# rc_filter_v1-xld50.net
KiCad netlist of a schematic drawn in EAGLE
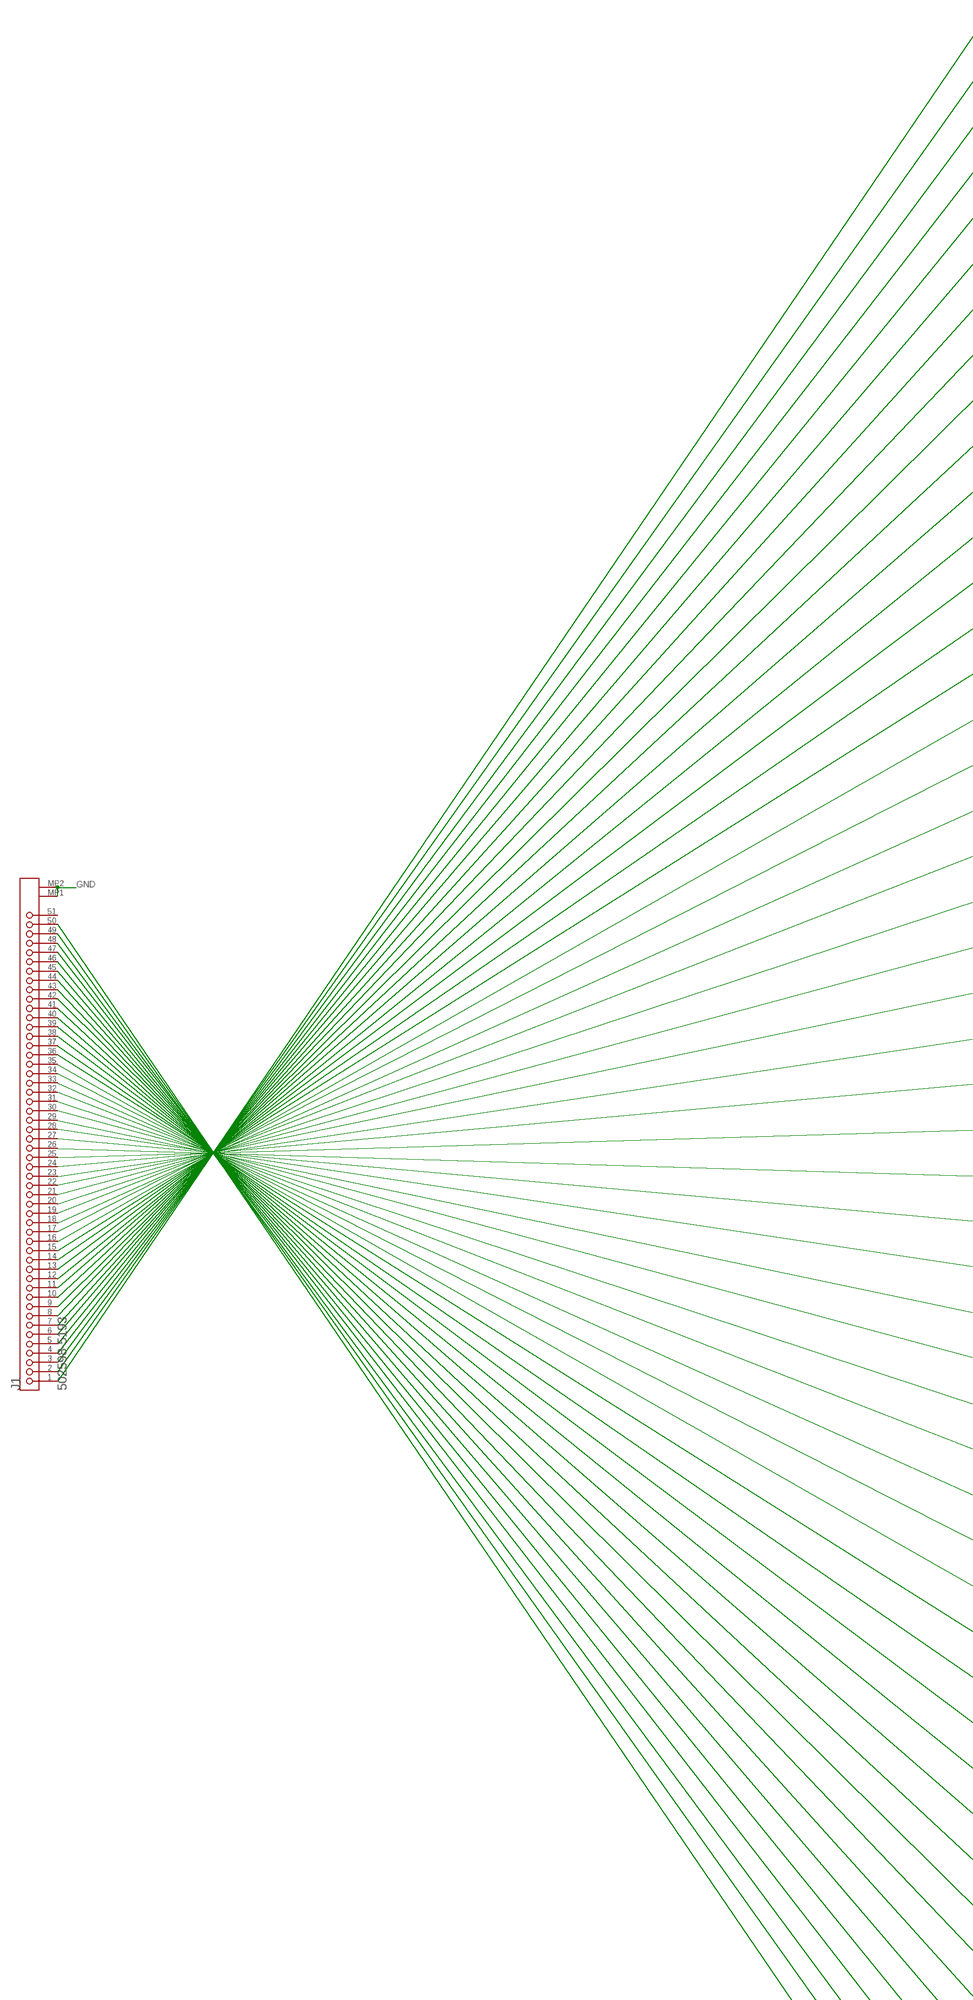
[diagram p0: schematic, sheet 1, part 1 of 3]
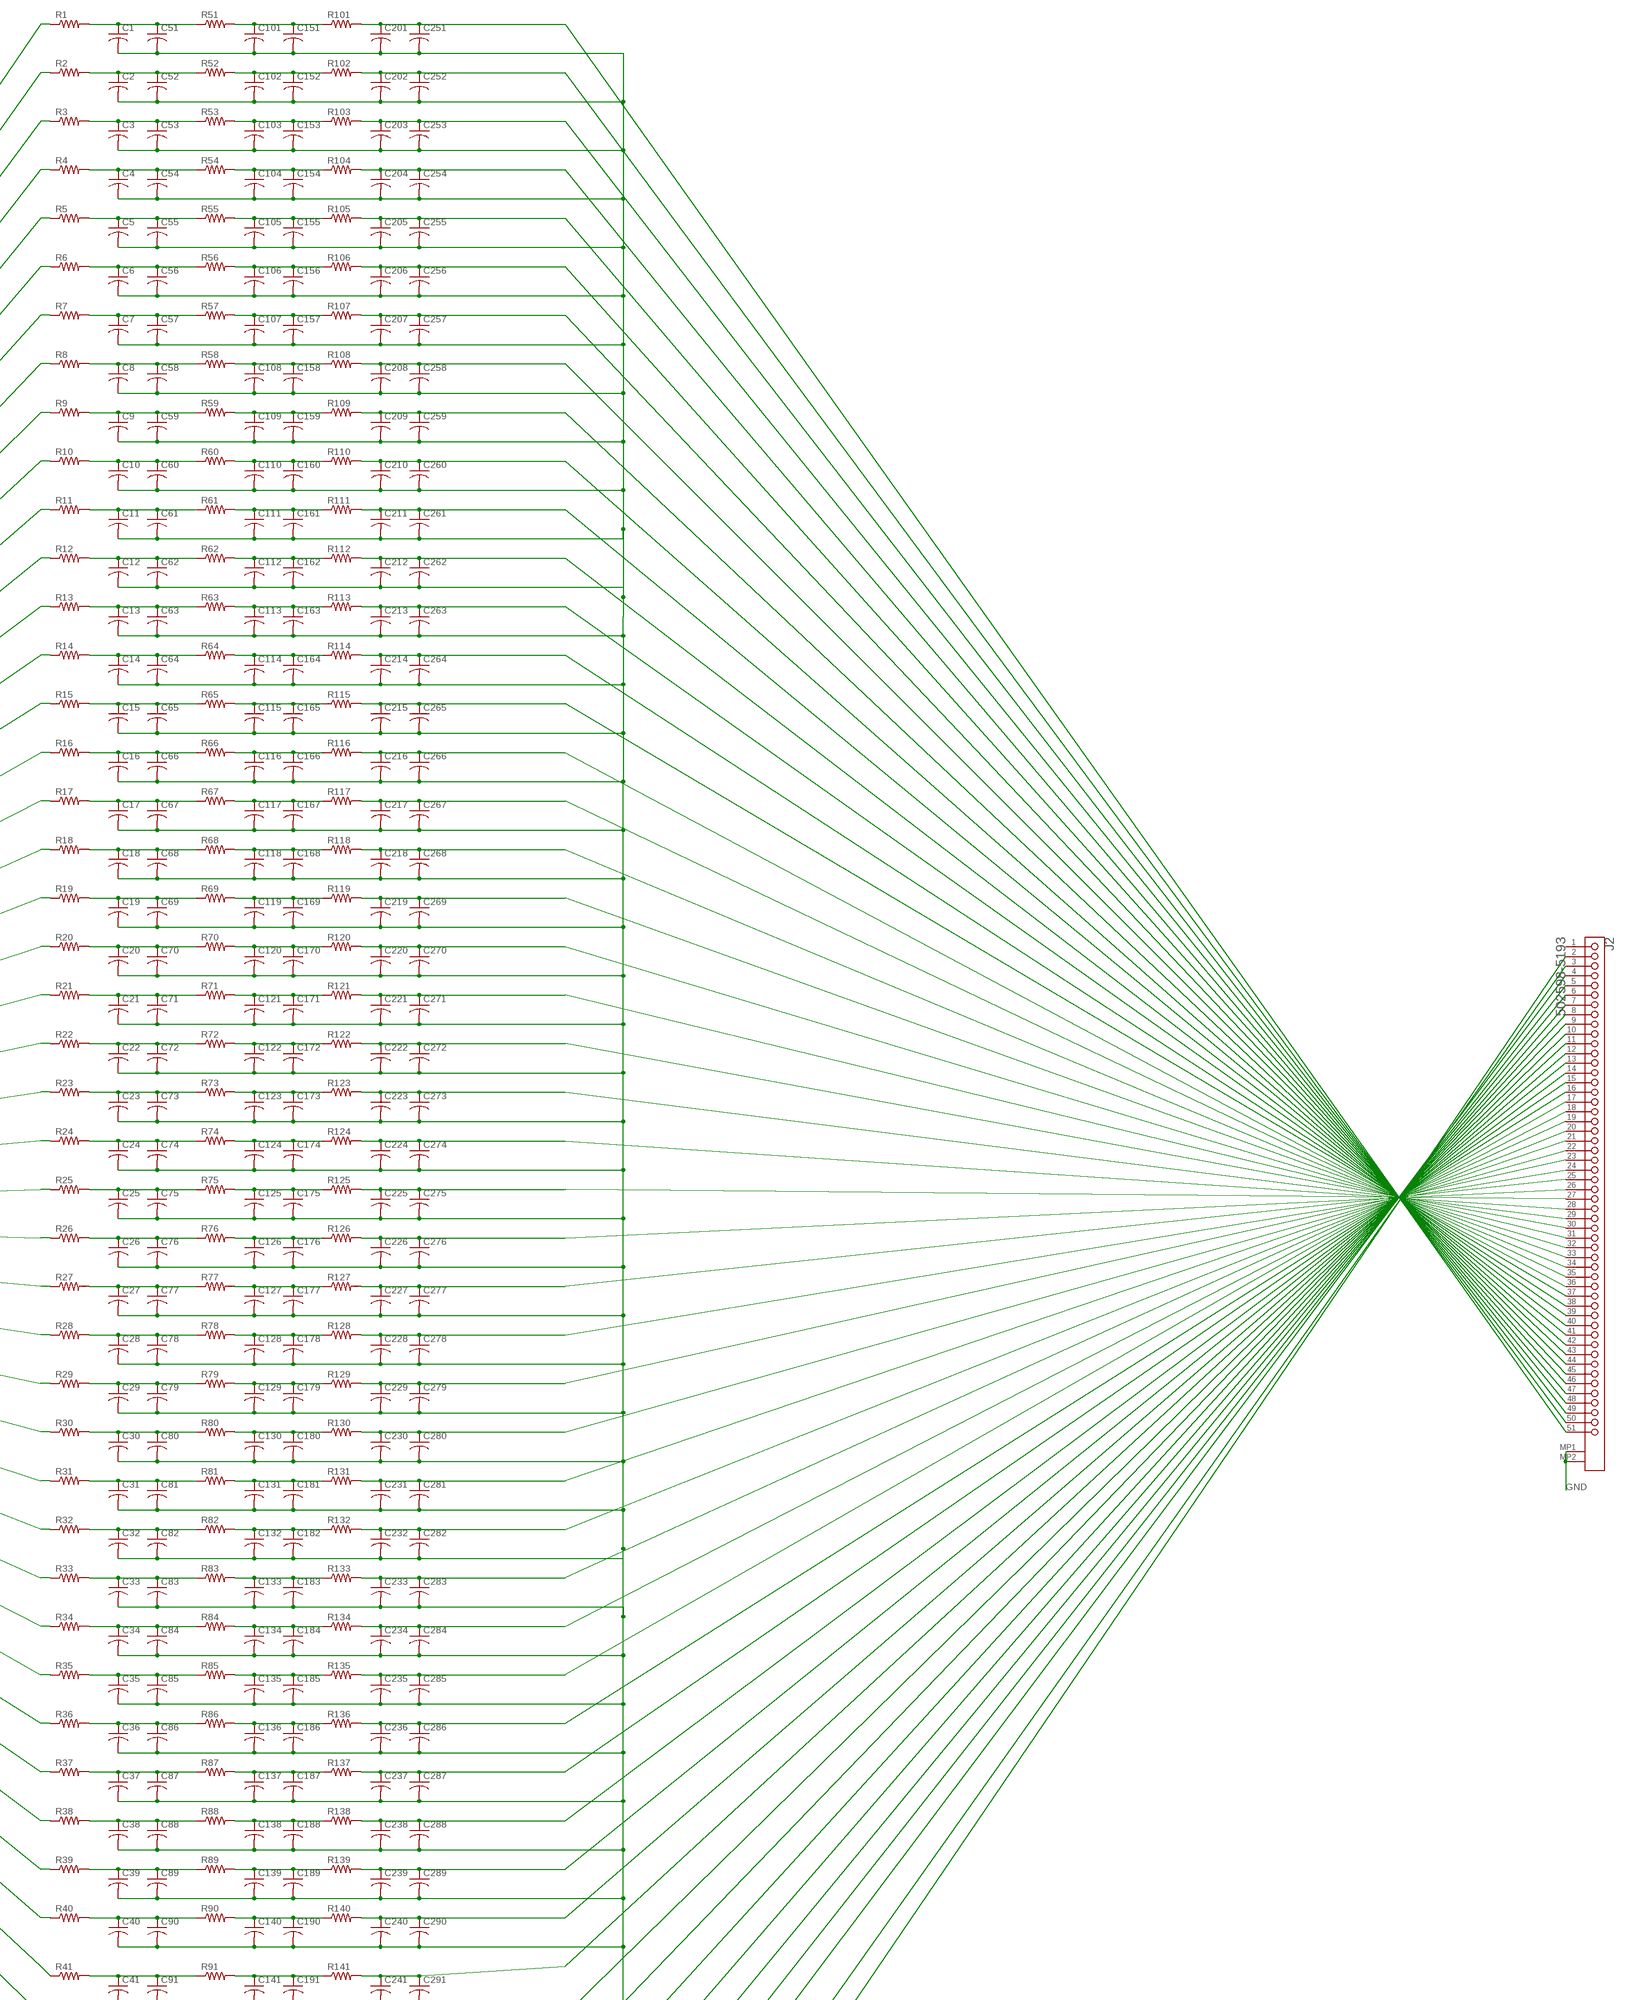
[diagram p1: schematic, sheet 1, part 2 of 3]
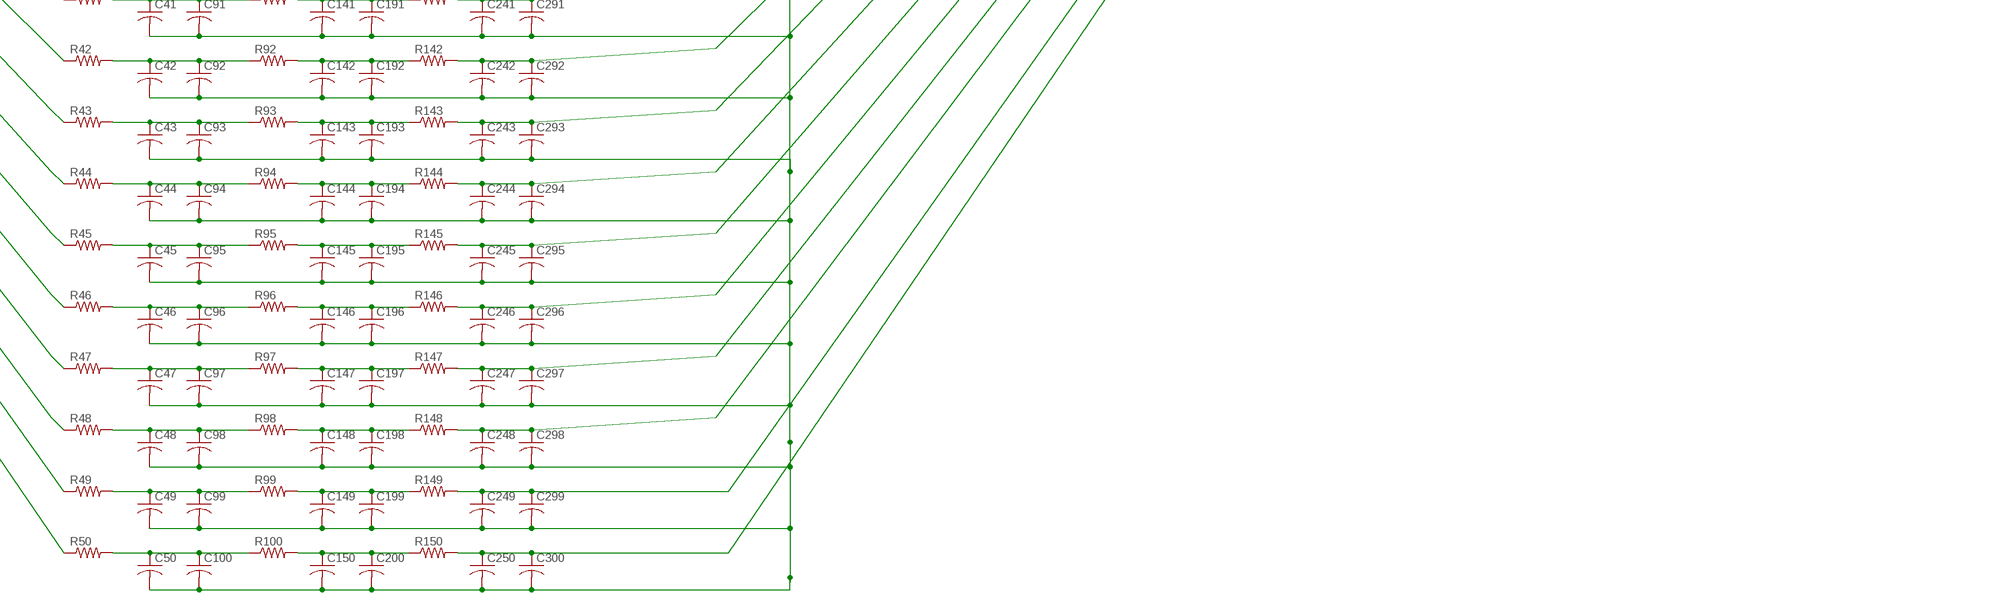
[diagram p2: schematic, sheet 1, part 3 of 3]

(export (version "E")
  (design (tool "Eeschema 10.0.6"))
  (components
    (comp (ref "C1")
      (value "C-USC0402")
      (footprint "eagle-import:C0402")
      (libsource (lib "eagle-import") (part "C-USC0402"))
    )
    (comp (ref "C2")
      (value "C-USC0402")
      (footprint "eagle-import:C0402")
      (libsource (lib "eagle-import") (part "C-USC0402"))
    )
    (comp (ref "C3")
      (value "C-USC0402")
      (footprint "eagle-import:C0402")
      (libsource (lib "eagle-import") (part "C-USC0402"))
    )
    (comp (ref "C4")
      (value "C-USC0402")
      (footprint "eagle-import:C0402")
      (libsource (lib "eagle-import") (part "C-USC0402"))
    )
    (comp (ref "C5")
      (value "C-USC0402")
      (footprint "eagle-import:C0402")
      (libsource (lib "eagle-import") (part "C-USC0402"))
    )
    (comp (ref "C6")
      (value "C-USC0402")
      (footprint "eagle-import:C0402")
      (libsource (lib "eagle-import") (part "C-USC0402"))
    )
    (comp (ref "C7")
      (value "C-USC0402")
      (footprint "eagle-import:C0402")
      (libsource (lib "eagle-import") (part "C-USC0402"))
    )
    (comp (ref "C8")
      (value "C-USC0402")
      (footprint "eagle-import:C0402")
      (libsource (lib "eagle-import") (part "C-USC0402"))
    )
    (comp (ref "C9")
      (value "C-USC0402")
      (footprint "eagle-import:C0402")
      (libsource (lib "eagle-import") (part "C-USC0402"))
    )
    (comp (ref "C10")
      (value "C-USC0402")
      (footprint "eagle-import:C0402")
      (libsource (lib "eagle-import") (part "C-USC0402"))
    )
    (comp (ref "C11")
      (value "C-USC0402")
      (footprint "eagle-import:C0402")
      (libsource (lib "eagle-import") (part "C-USC0402"))
    )
    (comp (ref "C12")
      (value "C-USC0402")
      (footprint "eagle-import:C0402")
      (libsource (lib "eagle-import") (part "C-USC0402"))
    )
    (comp (ref "C13")
      (value "C-USC0402")
      (footprint "eagle-import:C0402")
      (libsource (lib "eagle-import") (part "C-USC0402"))
    )
    (comp (ref "C14")
      (value "C-USC0402")
      (footprint "eagle-import:C0402")
      (libsource (lib "eagle-import") (part "C-USC0402"))
    )
    (comp (ref "C15")
      (value "C-USC0402")
      (footprint "eagle-import:C0402")
      (libsource (lib "eagle-import") (part "C-USC0402"))
    )
    (comp (ref "C16")
      (value "C-USC0402")
      (footprint "eagle-import:C0402")
      (libsource (lib "eagle-import") (part "C-USC0402"))
    )
    (comp (ref "C17")
      (value "C-USC0402")
      (footprint "eagle-import:C0402")
      (libsource (lib "eagle-import") (part "C-USC0402"))
    )
    (comp (ref "C18")
      (value "C-USC0402")
      (footprint "eagle-import:C0402")
      (libsource (lib "eagle-import") (part "C-USC0402"))
    )
    (comp (ref "C19")
      (value "C-USC0402")
      (footprint "eagle-import:C0402")
      (libsource (lib "eagle-import") (part "C-USC0402"))
    )
    (comp (ref "C20")
      (value "C-USC0402")
      (footprint "eagle-import:C0402")
      (libsource (lib "eagle-import") (part "C-USC0402"))
    )
    (comp (ref "C21")
      (value "C-USC0402")
      (footprint "eagle-import:C0402")
      (libsource (lib "eagle-import") (part "C-USC0402"))
    )
    (comp (ref "C22")
      (value "C-USC0402")
      (footprint "eagle-import:C0402")
      (libsource (lib "eagle-import") (part "C-USC0402"))
    )
    (comp (ref "C23")
      (value "C-USC0402")
      (footprint "eagle-import:C0402")
      (libsource (lib "eagle-import") (part "C-USC0402"))
    )
    (comp (ref "C24")
      (value "C-USC0402")
      (footprint "eagle-import:C0402")
      (libsource (lib "eagle-import") (part "C-USC0402"))
    )
    (comp (ref "C25")
      (value "C-USC0402")
      (footprint "eagle-import:C0402")
      (libsource (lib "eagle-import") (part "C-USC0402"))
    )
    (comp (ref "C26")
      (value "C-USC0402")
      (footprint "eagle-import:C0402")
      (libsource (lib "eagle-import") (part "C-USC0402"))
    )
    (comp (ref "C27")
      (value "C-USC0402")
      (footprint "eagle-import:C0402")
      (libsource (lib "eagle-import") (part "C-USC0402"))
    )
    (comp (ref "C28")
      (value "C-USC0402")
      (footprint "eagle-import:C0402")
      (libsource (lib "eagle-import") (part "C-USC0402"))
    )
    (comp (ref "C29")
      (value "C-USC0402")
      (footprint "eagle-import:C0402")
      (libsource (lib "eagle-import") (part "C-USC0402"))
    )
    (comp (ref "C30")
      (value "C-USC0402")
      (footprint "eagle-import:C0402")
      (libsource (lib "eagle-import") (part "C-USC0402"))
    )
    (comp (ref "C31")
      (value "C-USC0402")
      (footprint "eagle-import:C0402")
      (libsource (lib "eagle-import") (part "C-USC0402"))
    )
    (comp (ref "C32")
      (value "C-USC0402")
      (footprint "eagle-import:C0402")
      (libsource (lib "eagle-import") (part "C-USC0402"))
    )
    (comp (ref "C33")
      (value "C-USC0402")
      (footprint "eagle-import:C0402")
      (libsource (lib "eagle-import") (part "C-USC0402"))
    )
    (comp (ref "C34")
      (value "C-USC0402")
      (footprint "eagle-import:C0402")
      (libsource (lib "eagle-import") (part "C-USC0402"))
    )
    (comp (ref "C35")
      (value "C-USC0402")
      (footprint "eagle-import:C0402")
      (libsource (lib "eagle-import") (part "C-USC0402"))
    )
    (comp (ref "C36")
      (value "C-USC0402")
      (footprint "eagle-import:C0402")
      (libsource (lib "eagle-import") (part "C-USC0402"))
    )
    (comp (ref "C37")
      (value "C-USC0402")
      (footprint "eagle-import:C0402")
      (libsource (lib "eagle-import") (part "C-USC0402"))
    )
    (comp (ref "C38")
      (value "C-USC0402")
      (footprint "eagle-import:C0402")
      (libsource (lib "eagle-import") (part "C-USC0402"))
    )
    (comp (ref "C39")
      (value "C-USC0402")
      (footprint "eagle-import:C0402")
      (libsource (lib "eagle-import") (part "C-USC0402"))
    )
    (comp (ref "C40")
      (value "C-USC0402")
      (footprint "eagle-import:C0402")
      (libsource (lib "eagle-import") (part "C-USC0402"))
    )
    (comp (ref "C41")
      (value "C-USC0402")
      (footprint "eagle-import:C0402")
      (libsource (lib "eagle-import") (part "C-USC0402"))
    )
    (comp (ref "C42")
      (value "C-USC0402")
      (footprint "eagle-import:C0402")
      (libsource (lib "eagle-import") (part "C-USC0402"))
    )
    (comp (ref "C43")
      (value "C-USC0402")
      (footprint "eagle-import:C0402")
      (libsource (lib "eagle-import") (part "C-USC0402"))
    )
    (comp (ref "C44")
      (value "C-USC0402")
      (footprint "eagle-import:C0402")
      (libsource (lib "eagle-import") (part "C-USC0402"))
    )
    (comp (ref "C45")
      (value "C-USC0402")
      (footprint "eagle-import:C0402")
      (libsource (lib "eagle-import") (part "C-USC0402"))
    )
    (comp (ref "C46")
      (value "C-USC0402")
      (footprint "eagle-import:C0402")
      (libsource (lib "eagle-import") (part "C-USC0402"))
    )
    (comp (ref "C47")
      (value "C-USC0402")
      (footprint "eagle-import:C0402")
      (libsource (lib "eagle-import") (part "C-USC0402"))
    )
    (comp (ref "C48")
      (value "C-USC0402")
      (footprint "eagle-import:C0402")
      (libsource (lib "eagle-import") (part "C-USC0402"))
    )
    (comp (ref "C49")
      (value "C-USC0402")
      (footprint "eagle-import:C0402")
      (libsource (lib "eagle-import") (part "C-USC0402"))
    )
    (comp (ref "C50")
      (value "C-USC0402")
      (footprint "eagle-import:C0402")
      (libsource (lib "eagle-import") (part "C-USC0402"))
    )
    (comp (ref "C51")
      (value "C-USC0402")
      (footprint "eagle-import:C0402")
      (libsource (lib "eagle-import") (part "C-USC0402"))
    )
    (comp (ref "C52")
      (value "C-USC0402")
      (footprint "eagle-import:C0402")
      (libsource (lib "eagle-import") (part "C-USC0402"))
    )
    (comp (ref "C53")
      (value "C-USC0402")
      (footprint "eagle-import:C0402")
      (libsource (lib "eagle-import") (part "C-USC0402"))
    )
    (comp (ref "C54")
      (value "C-USC0402")
      (footprint "eagle-import:C0402")
      (libsource (lib "eagle-import") (part "C-USC0402"))
    )
    (comp (ref "C55")
      (value "C-USC0402")
      (footprint "eagle-import:C0402")
      (libsource (lib "eagle-import") (part "C-USC0402"))
    )
    (comp (ref "C56")
      (value "C-USC0402")
      (footprint "eagle-import:C0402")
      (libsource (lib "eagle-import") (part "C-USC0402"))
    )
    (comp (ref "C57")
      (value "C-USC0402")
      (footprint "eagle-import:C0402")
      (libsource (lib "eagle-import") (part "C-USC0402"))
    )
    (comp (ref "C58")
      (value "C-USC0402")
      (footprint "eagle-import:C0402")
      (libsource (lib "eagle-import") (part "C-USC0402"))
    )
    (comp (ref "C59")
      (value "C-USC0402")
      (footprint "eagle-import:C0402")
      (libsource (lib "eagle-import") (part "C-USC0402"))
    )
    (comp (ref "C60")
      (value "C-USC0402")
      (footprint "eagle-import:C0402")
      (libsource (lib "eagle-import") (part "C-USC0402"))
    )
    (comp (ref "C61")
      (value "C-USC0402")
      (footprint "eagle-import:C0402")
      (libsource (lib "eagle-import") (part "C-USC0402"))
    )
    (comp (ref "C62")
      (value "C-USC0402")
      (footprint "eagle-import:C0402")
      (libsource (lib "eagle-import") (part "C-USC0402"))
    )
    (comp (ref "C63")
      (value "C-USC0402")
      (footprint "eagle-import:C0402")
      (libsource (lib "eagle-import") (part "C-USC0402"))
    )
    (comp (ref "C64")
      (value "C-USC0402")
      (footprint "eagle-import:C0402")
      (libsource (lib "eagle-import") (part "C-USC0402"))
    )
    (comp (ref "C65")
      (value "C-USC0402")
      (footprint "eagle-import:C0402")
      (libsource (lib "eagle-import") (part "C-USC0402"))
    )
    (comp (ref "C66")
      (value "C-USC0402")
      (footprint "eagle-import:C0402")
      (libsource (lib "eagle-import") (part "C-USC0402"))
    )
    (comp (ref "C67")
      (value "C-USC0402")
      (footprint "eagle-import:C0402")
      (libsource (lib "eagle-import") (part "C-USC0402"))
    )
    (comp (ref "C68")
      (value "C-USC0402")
      (footprint "eagle-import:C0402")
      (libsource (lib "eagle-import") (part "C-USC0402"))
    )
    (comp (ref "C69")
      (value "C-USC0402")
      (footprint "eagle-import:C0402")
      (libsource (lib "eagle-import") (part "C-USC0402"))
    )
    (comp (ref "C70")
      (value "C-USC0402")
      (footprint "eagle-import:C0402")
      (libsource (lib "eagle-import") (part "C-USC0402"))
    )
    (comp (ref "C71")
      (value "C-USC0402")
      (footprint "eagle-import:C0402")
      (libsource (lib "eagle-import") (part "C-USC0402"))
    )
    (comp (ref "C72")
      (value "C-USC0402")
      (footprint "eagle-import:C0402")
      (libsource (lib "eagle-import") (part "C-USC0402"))
    )
    (comp (ref "C73")
      (value "C-USC0402")
      (footprint "eagle-import:C0402")
      (libsource (lib "eagle-import") (part "C-USC0402"))
    )
    (comp (ref "C74")
      (value "C-USC0402")
      (footprint "eagle-import:C0402")
      (libsource (lib "eagle-import") (part "C-USC0402"))
    )
    (comp (ref "C75")
      (value "C-USC0402")
      (footprint "eagle-import:C0402")
      (libsource (lib "eagle-import") (part "C-USC0402"))
    )
    (comp (ref "C76")
      (value "C-USC0402")
      (footprint "eagle-import:C0402")
      (libsource (lib "eagle-import") (part "C-USC0402"))
    )
    (comp (ref "C77")
      (value "C-USC0402")
      (footprint "eagle-import:C0402")
      (libsource (lib "eagle-import") (part "C-USC0402"))
    )
    (comp (ref "C78")
      (value "C-USC0402")
      (footprint "eagle-import:C0402")
      (libsource (lib "eagle-import") (part "C-USC0402"))
    )
    (comp (ref "C79")
      (value "C-USC0402")
      (footprint "eagle-import:C0402")
      (libsource (lib "eagle-import") (part "C-USC0402"))
    )
    (comp (ref "C80")
      (value "C-USC0402")
      (footprint "eagle-import:C0402")
      (libsource (lib "eagle-import") (part "C-USC0402"))
    )
    (comp (ref "C81")
      (value "C-USC0402")
      (footprint "eagle-import:C0402")
      (libsource (lib "eagle-import") (part "C-USC0402"))
    )
    (comp (ref "C82")
      (value "C-USC0402")
      (footprint "eagle-import:C0402")
      (libsource (lib "eagle-import") (part "C-USC0402"))
    )
    (comp (ref "C83")
      (value "C-USC0402")
      (footprint "eagle-import:C0402")
      (libsource (lib "eagle-import") (part "C-USC0402"))
    )
    (comp (ref "C84")
      (value "C-USC0402")
      (footprint "eagle-import:C0402")
      (libsource (lib "eagle-import") (part "C-USC0402"))
    )
    (comp (ref "C85")
      (value "C-USC0402")
      (footprint "eagle-import:C0402")
      (libsource (lib "eagle-import") (part "C-USC0402"))
    )
    (comp (ref "C86")
      (value "C-USC0402")
      (footprint "eagle-import:C0402")
      (libsource (lib "eagle-import") (part "C-USC0402"))
    )
    (comp (ref "C87")
      (value "C-USC0402")
      (footprint "eagle-import:C0402")
      (libsource (lib "eagle-import") (part "C-USC0402"))
    )
    (comp (ref "C88")
      (value "C-USC0402")
      (footprint "eagle-import:C0402")
      (libsource (lib "eagle-import") (part "C-USC0402"))
    )
    (comp (ref "C89")
      (value "C-USC0402")
      (footprint "eagle-import:C0402")
      (libsource (lib "eagle-import") (part "C-USC0402"))
    )
    (comp (ref "C90")
      (value "C-USC0402")
      (footprint "eagle-import:C0402")
      (libsource (lib "eagle-import") (part "C-USC0402"))
    )
    (comp (ref "C91")
      (value "C-USC0402")
      (footprint "eagle-import:C0402")
      (libsource (lib "eagle-import") (part "C-USC0402"))
    )
    (comp (ref "C92")
      (value "C-USC0402")
      (footprint "eagle-import:C0402")
      (libsource (lib "eagle-import") (part "C-USC0402"))
    )
    (comp (ref "C93")
      (value "C-USC0402")
      (footprint "eagle-import:C0402")
      (libsource (lib "eagle-import") (part "C-USC0402"))
    )
    (comp (ref "C94")
      (value "C-USC0402")
      (footprint "eagle-import:C0402")
      (libsource (lib "eagle-import") (part "C-USC0402"))
    )
    (comp (ref "C95")
      (value "C-USC0402")
      (footprint "eagle-import:C0402")
      (libsource (lib "eagle-import") (part "C-USC0402"))
    )
    (comp (ref "C96")
      (value "C-USC0402")
      (footprint "eagle-import:C0402")
      (libsource (lib "eagle-import") (part "C-USC0402"))
    )
    (comp (ref "C97")
      (value "C-USC0402")
      (footprint "eagle-import:C0402")
      (libsource (lib "eagle-import") (part "C-USC0402"))
    )
    (comp (ref "C98")
      (value "C-USC0402")
      (footprint "eagle-import:C0402")
      (libsource (lib "eagle-import") (part "C-USC0402"))
    )
    (comp (ref "C99")
      (value "C-USC0402")
      (footprint "eagle-import:C0402")
      (libsource (lib "eagle-import") (part "C-USC0402"))
    )
    (comp (ref "C100")
      (value "C-USC0402")
      (footprint "eagle-import:C0402")
      (libsource (lib "eagle-import") (part "C-USC0402"))
    )
    (comp (ref "C101")
      (value "C-USC0402")
      (footprint "eagle-import:C0402")
      (libsource (lib "eagle-import") (part "C-USC0402"))
    )
    (comp (ref "C102")
      (value "C-USC0402")
      (footprint "eagle-import:C0402")
      (libsource (lib "eagle-import") (part "C-USC0402"))
    )
    (comp (ref "C103")
      (value "C-USC0402")
      (footprint "eagle-import:C0402")
      (libsource (lib "eagle-import") (part "C-USC0402"))
    )
    (comp (ref "C104")
      (value "C-USC0402")
      (footprint "eagle-import:C0402")
      (libsource (lib "eagle-import") (part "C-USC0402"))
    )
    (comp (ref "C105")
      (value "C-USC0402")
      (footprint "eagle-import:C0402")
      (libsource (lib "eagle-import") (part "C-USC0402"))
    )
    (comp (ref "C106")
      (value "C-USC0402")
      (footprint "eagle-import:C0402")
      (libsource (lib "eagle-import") (part "C-USC0402"))
    )
    (comp (ref "C107")
      (value "C-USC0402")
      (footprint "eagle-import:C0402")
      (libsource (lib "eagle-import") (part "C-USC0402"))
    )
    (comp (ref "C108")
      (value "C-USC0402")
      (footprint "eagle-import:C0402")
      (libsource (lib "eagle-import") (part "C-USC0402"))
    )
    (comp (ref "C109")
      (value "C-USC0402")
      (footprint "eagle-import:C0402")
      (libsource (lib "eagle-import") (part "C-USC0402"))
    )
    (comp (ref "C110")
      (value "C-USC0402")
      (footprint "eagle-import:C0402")
      (libsource (lib "eagle-import") (part "C-USC0402"))
    )
    (comp (ref "C111")
      (value "C-USC0402")
      (footprint "eagle-import:C0402")
      (libsource (lib "eagle-import") (part "C-USC0402"))
    )
    (comp (ref "C112")
      (value "C-USC0402")
      (footprint "eagle-import:C0402")
      (libsource (lib "eagle-import") (part "C-USC0402"))
    )
    (comp (ref "C113")
      (value "C-USC0402")
      (footprint "eagle-import:C0402")
      (libsource (lib "eagle-import") (part "C-USC0402"))
    )
    (comp (ref "C114")
      (value "C-USC0402")
      (footprint "eagle-import:C0402")
      (libsource (lib "eagle-import") (part "C-USC0402"))
    )
    (comp (ref "C115")
      (value "C-USC0402")
      (footprint "eagle-import:C0402")
      (libsource (lib "eagle-import") (part "C-USC0402"))
    )
    (comp (ref "C116")
      (value "C-USC0402")
      (footprint "eagle-import:C0402")
      (libsource (lib "eagle-import") (part "C-USC0402"))
    )
    (comp (ref "C117")
      (value "C-USC0402")
      (footprint "eagle-import:C0402")
      (libsource (lib "eagle-import") (part "C-USC0402"))
    )
    (comp (ref "C118")
      (value "C-USC0402")
      (footprint "eagle-import:C0402")
      (libsource (lib "eagle-import") (part "C-USC0402"))
    )
    (comp (ref "C119")
      (value "C-USC0402")
      (footprint "eagle-import:C0402")
      (libsource (lib "eagle-import") (part "C-USC0402"))
    )
    (comp (ref "C120")
      (value "C-USC0402")
      (footprint "eagle-import:C0402")
      (libsource (lib "eagle-import") (part "C-USC0402"))
    )
    (comp (ref "C121")
      (value "C-USC0402")
      (footprint "eagle-import:C0402")
      (libsource (lib "eagle-import") (part "C-USC0402"))
    )
    (comp (ref "C122")
      (value "C-USC0402")
      (footprint "eagle-import:C0402")
      (libsource (lib "eagle-import") (part "C-USC0402"))
    )
    (comp (ref "C123")
      (value "C-USC0402")
      (footprint "eagle-import:C0402")
      (libsource (lib "eagle-import") (part "C-USC0402"))
    )
    (comp (ref "C124")
      (value "C-USC0402")
      (footprint "eagle-import:C0402")
      (libsource (lib "eagle-import") (part "C-USC0402"))
    )
    (comp (ref "C125")
      (value "C-USC0402")
      (footprint "eagle-import:C0402")
      (libsource (lib "eagle-import") (part "C-USC0402"))
    )
    (comp (ref "C126")
      (value "C-USC0402")
      (footprint "eagle-import:C0402")
      (libsource (lib "eagle-import") (part "C-USC0402"))
    )
    (comp (ref "C127")
      (value "C-USC0402")
      (footprint "eagle-import:C0402")
      (libsource (lib "eagle-import") (part "C-USC0402"))
    )
    (comp (ref "C128")
      (value "C-USC0402")
      (footprint "eagle-import:C0402")
      (libsource (lib "eagle-import") (part "C-USC0402"))
    )
    (comp (ref "C129")
      (value "C-USC0402")
      (footprint "eagle-import:C0402")
      (libsource (lib "eagle-import") (part "C-USC0402"))
    )
    (comp (ref "C130")
      (value "C-USC0402")
      (footprint "eagle-import:C0402")
      (libsource (lib "eagle-import") (part "C-USC0402"))
    )
    (comp (ref "C131")
      (value "C-USC0402")
      (footprint "eagle-import:C0402")
      (libsource (lib "eagle-import") (part "C-USC0402"))
    )
    (comp (ref "C132")
      (value "C-USC0402")
      (footprint "eagle-import:C0402")
      (libsource (lib "eagle-import") (part "C-USC0402"))
    )
    (comp (ref "C133")
      (value "C-USC0402")
      (footprint "eagle-import:C0402")
      (libsource (lib "eagle-import") (part "C-USC0402"))
    )
    (comp (ref "C134")
      (value "C-USC0402")
      (footprint "eagle-import:C0402")
      (libsource (lib "eagle-import") (part "C-USC0402"))
    )
    (comp (ref "C135")
      (value "C-USC0402")
      (footprint "eagle-import:C0402")
      (libsource (lib "eagle-import") (part "C-USC0402"))
    )
    (comp (ref "C136")
      (value "C-USC0402")
      (footprint "eagle-import:C0402")
      (libsource (lib "eagle-import") (part "C-USC0402"))
    )
    (comp (ref "C137")
      (value "C-USC0402")
      (footprint "eagle-import:C0402")
      (libsource (lib "eagle-import") (part "C-USC0402"))
    )
    (comp (ref "C138")
      (value "C-USC0402")
      (footprint "eagle-import:C0402")
      (libsource (lib "eagle-import") (part "C-USC0402"))
    )
    (comp (ref "C139")
      (value "C-USC0402")
      (footprint "eagle-import:C0402")
      (libsource (lib "eagle-import") (part "C-USC0402"))
    )
    (comp (ref "C140")
      (value "C-USC0402")
      (footprint "eagle-import:C0402")
      (libsource (lib "eagle-import") (part "C-USC0402"))
    )
    (comp (ref "C141")
      (value "C-USC0402")
      (footprint "eagle-import:C0402")
      (libsource (lib "eagle-import") (part "C-USC0402"))
    )
    (comp (ref "C142")
      (value "C-USC0402")
      (footprint "eagle-import:C0402")
      (libsource (lib "eagle-import") (part "C-USC0402"))
    )
    (comp (ref "C143")
      (value "C-USC0402")
      (footprint "eagle-import:C0402")
      (libsource (lib "eagle-import") (part "C-USC0402"))
    )
    (comp (ref "C144")
      (value "C-USC0402")
      (footprint "eagle-import:C0402")
      (libsource (lib "eagle-import") (part "C-USC0402"))
    )
    (comp (ref "C145")
      (value "C-USC0402")
      (footprint "eagle-import:C0402")
      (libsource (lib "eagle-import") (part "C-USC0402"))
    )
    (comp (ref "C146")
      (value "C-USC0402")
      (footprint "eagle-import:C0402")
      (libsource (lib "eagle-import") (part "C-USC0402"))
    )
    (comp (ref "C147")
      (value "C-USC0402")
      (footprint "eagle-import:C0402")
      (libsource (lib "eagle-import") (part "C-USC0402"))
    )
    (comp (ref "C148")
      (value "C-USC0402")
      (footprint "eagle-import:C0402")
      (libsource (lib "eagle-import") (part "C-USC0402"))
    )
    (comp (ref "C149")
      (value "C-USC0402")
      (footprint "eagle-import:C0402")
      (libsource (lib "eagle-import") (part "C-USC0402"))
    )
    (comp (ref "C150")
      (value "C-USC0402")
      (footprint "eagle-import:C0402")
      (libsource (lib "eagle-import") (part "C-USC0402"))
    )
    (comp (ref "C151")
      (value "C-USC0402")
      (footprint "eagle-import:C0402")
      (libsource (lib "eagle-import") (part "C-USC0402"))
    )
    (comp (ref "C152")
      (value "C-USC0402")
      (footprint "eagle-import:C0402")
      (libsource (lib "eagle-import") (part "C-USC0402"))
    )
    (comp (ref "C153")
      (value "C-USC0402")
      (footprint "eagle-import:C0402")
      (libsource (lib "eagle-import") (part "C-USC0402"))
    )
    (comp (ref "C154")
      (value "C-USC0402")
      (footprint "eagle-import:C0402")
      (libsource (lib "eagle-import") (part "C-USC0402"))
    )
    (comp (ref "C155")
      (value "C-USC0402")
      (footprint "eagle-import:C0402")
      (libsource (lib "eagle-import") (part "C-USC0402"))
    )
    (comp (ref "C156")
      (value "C-USC0402")
      (footprint "eagle-import:C0402")
      (libsource (lib "eagle-import") (part "C-USC0402"))
    )
    (comp (ref "C157")
      (value "C-USC0402")
      (footprint "eagle-import:C0402")
      (libsource (lib "eagle-import") (part "C-USC0402"))
    )
    (comp (ref "C158")
      (value "C-USC0402")
      (footprint "eagle-import:C0402")
      (libsource (lib "eagle-import") (part "C-USC0402"))
    )
    (comp (ref "C159")
      (value "C-USC0402")
      (footprint "eagle-import:C0402")
      (libsource (lib "eagle-import") (part "C-USC0402"))
    )
    (comp (ref "C160")
      (value "C-USC0402")
      (footprint "eagle-import:C0402")
      (libsource (lib "eagle-import") (part "C-USC0402"))
    )
    (comp (ref "C161")
      (value "C-USC0402")
      (footprint "eagle-import:C0402")
      (libsource (lib "eagle-import") (part "C-USC0402"))
    )
    (comp (ref "C162")
      (value "C-USC0402")
      (footprint "eagle-import:C0402")
      (libsource (lib "eagle-import") (part "C-USC0402"))
    )
    (comp (ref "C163")
      (value "C-USC0402")
      (footprint "eagle-import:C0402")
      (libsource (lib "eagle-import") (part "C-USC0402"))
    )
    (comp (ref "C164")
      (value "C-USC0402")
      (footprint "eagle-import:C0402")
      (libsource (lib "eagle-import") (part "C-USC0402"))
    )
    (comp (ref "C165")
      (value "C-USC0402")
      (footprint "eagle-import:C0402")
      (libsource (lib "eagle-import") (part "C-USC0402"))
    )
    (comp (ref "C166")
      (value "C-USC0402")
      (footprint "eagle-import:C0402")
      (libsource (lib "eagle-import") (part "C-USC0402"))
    )
    (comp (ref "C167")
      (value "C-USC0402")
      (footprint "eagle-import:C0402")
      (libsource (lib "eagle-import") (part "C-USC0402"))
    )
    (comp (ref "C168")
      (value "C-USC0402")
      (footprint "eagle-import:C0402")
      (libsource (lib "eagle-import") (part "C-USC0402"))
    )
    (comp (ref "C169")
      (value "C-USC0402")
      (footprint "eagle-import:C0402")
      (libsource (lib "eagle-import") (part "C-USC0402"))
    )
    (comp (ref "C170")
      (value "C-USC0402")
      (footprint "eagle-import:C0402")
      (libsource (lib "eagle-import") (part "C-USC0402"))
    )
    (comp (ref "C171")
      (value "C-USC0402")
      (footprint "eagle-import:C0402")
      (libsource (lib "eagle-import") (part "C-USC0402"))
    )
    (comp (ref "C172")
      (value "C-USC0402")
      (footprint "eagle-import:C0402")
      (libsource (lib "eagle-import") (part "C-USC0402"))
    )
    (comp (ref "C173")
      (value "C-USC0402")
      (footprint "eagle-import:C0402")
      (libsource (lib "eagle-import") (part "C-USC0402"))
    )
    (comp (ref "C174")
      (value "C-USC0402")
      (footprint "eagle-import:C0402")
      (libsource (lib "eagle-import") (part "C-USC0402"))
    )
    (comp (ref "C175")
      (value "C-USC0402")
      (footprint "eagle-import:C0402")
      (libsource (lib "eagle-import") (part "C-USC0402"))
    )
    (comp (ref "C176")
      (value "C-USC0402")
      (footprint "eagle-import:C0402")
      (libsource (lib "eagle-import") (part "C-USC0402"))
    )
    (comp (ref "C177")
      (value "C-USC0402")
      (footprint "eagle-import:C0402")
      (libsource (lib "eagle-import") (part "C-USC0402"))
    )
    (comp (ref "C178")
      (value "C-USC0402")
      (footprint "eagle-import:C0402")
      (libsource (lib "eagle-import") (part "C-USC0402"))
    )
    (comp (ref "C179")
      (value "C-USC0402")
      (footprint "eagle-import:C0402")
      (libsource (lib "eagle-import") (part "C-USC0402"))
    )
    (comp (ref "C180")
      (value "C-USC0402")
      (footprint "eagle-import:C0402")
      (libsource (lib "eagle-import") (part "C-USC0402"))
    )
    (comp (ref "C181")
      (value "C-USC0402")
      (footprint "eagle-import:C0402")
      (libsource (lib "eagle-import") (part "C-USC0402"))
    )
    (comp (ref "C182")
      (value "C-USC0402")
      (footprint "eagle-import:C0402")
      (libsource (lib "eagle-import") (part "C-USC0402"))
    )
    (comp (ref "C183")
      (value "C-USC0402")
      (footprint "eagle-import:C0402")
      (libsource (lib "eagle-import") (part "C-USC0402"))
    )
    (comp (ref "C184")
      (value "C-USC0402")
      (footprint "eagle-import:C0402")
      (libsource (lib "eagle-import") (part "C-USC0402"))
    )
    (comp (ref "C185")
      (value "C-USC0402")
      (footprint "eagle-import:C0402")
      (libsource (lib "eagle-import") (part "C-USC0402"))
    )
    (comp (ref "C186")
      (value "C-USC0402")
      (footprint "eagle-import:C0402")
      (libsource (lib "eagle-import") (part "C-USC0402"))
    )
    (comp (ref "C187")
      (value "C-USC0402")
      (footprint "eagle-import:C0402")
      (libsource (lib "eagle-import") (part "C-USC0402"))
    )
    (comp (ref "C188")
      (value "C-USC0402")
      (footprint "eagle-import:C0402")
      (libsource (lib "eagle-import") (part "C-USC0402"))
    )
    (comp (ref "C189")
      (value "C-USC0402")
      (footprint "eagle-import:C0402")
      (libsource (lib "eagle-import") (part "C-USC0402"))
    )
    (comp (ref "C190")
      (value "C-USC0402")
      (footprint "eagle-import:C0402")
      (libsource (lib "eagle-import") (part "C-USC0402"))
    )
    (comp (ref "C191")
      (value "C-USC0402")
      (footprint "eagle-import:C0402")
      (libsource (lib "eagle-import") (part "C-USC0402"))
    )
    (comp (ref "C192")
      (value "C-USC0402")
      (footprint "eagle-import:C0402")
      (libsource (lib "eagle-import") (part "C-USC0402"))
    )
    (comp (ref "C193")
      (value "C-USC0402")
      (footprint "eagle-import:C0402")
      (libsource (lib "eagle-import") (part "C-USC0402"))
    )
    (comp (ref "C194")
      (value "C-USC0402")
      (footprint "eagle-import:C0402")
      (libsource (lib "eagle-import") (part "C-USC0402"))
    )
    (comp (ref "C195")
      (value "C-USC0402")
      (footprint "eagle-import:C0402")
      (libsource (lib "eagle-import") (part "C-USC0402"))
    )
    (comp (ref "C196")
      (value "C-USC0402")
      (footprint "eagle-import:C0402")
      (libsource (lib "eagle-import") (part "C-USC0402"))
    )
    (comp (ref "C197")
      (value "C-USC0402")
      (footprint "eagle-import:C0402")
      (libsource (lib "eagle-import") (part "C-USC0402"))
    )
    (comp (ref "C198")
      (value "C-USC0402")
      (footprint "eagle-import:C0402")
      (libsource (lib "eagle-import") (part "C-USC0402"))
    )
    (comp (ref "C199")
      (value "C-USC0402")
      (footprint "eagle-import:C0402")
      (libsource (lib "eagle-import") (part "C-USC0402"))
    )
    (comp (ref "C200")
      (value "C-USC0402")
      (footprint "eagle-import:C0402")
      (libsource (lib "eagle-import") (part "C-USC0402"))
    )
    (comp (ref "C201")
      (value "C-USC0402")
      (footprint "eagle-import:C0402")
      (libsource (lib "eagle-import") (part "C-USC0402"))
    )
    (comp (ref "C202")
      (value "C-USC0402")
      (footprint "eagle-import:C0402")
      (libsource (lib "eagle-import") (part "C-USC0402"))
    )
    (comp (ref "C203")
      (value "C-USC0402")
      (footprint "eagle-import:C0402")
      (libsource (lib "eagle-import") (part "C-USC0402"))
    )
    (comp (ref "C204")
      (value "C-USC0402")
      (footprint "eagle-import:C0402")
      (libsource (lib "eagle-import") (part "C-USC0402"))
    )
    (comp (ref "C205")
      (value "C-USC0402")
      (footprint "eagle-import:C0402")
      (libsource (lib "eagle-import") (part "C-USC0402"))
    )
    (comp (ref "C206")
      (value "C-USC0402")
      (footprint "eagle-import:C0402")
      (libsource (lib "eagle-import") (part "C-USC0402"))
    )
    (comp (ref "C207")
      (value "C-USC0402")
      (footprint "eagle-import:C0402")
      (libsource (lib "eagle-import") (part "C-USC0402"))
    )
    (comp (ref "C208")
      (value "C-USC0402")
      (footprint "eagle-import:C0402")
      (libsource (lib "eagle-import") (part "C-USC0402"))
    )
    (comp (ref "C209")
      (value "C-USC0402")
      (footprint "eagle-import:C0402")
      (libsource (lib "eagle-import") (part "C-USC0402"))
    )
    (comp (ref "C210")
      (value "C-USC0402")
      (footprint "eagle-import:C0402")
      (libsource (lib "eagle-import") (part "C-USC0402"))
    )
    (comp (ref "C211")
      (value "C-USC0402")
      (footprint "eagle-import:C0402")
      (libsource (lib "eagle-import") (part "C-USC0402"))
    )
    (comp (ref "C212")
      (value "C-USC0402")
      (footprint "eagle-import:C0402")
      (libsource (lib "eagle-import") (part "C-USC0402"))
    )
    (comp (ref "C213")
      (value "C-USC0402")
      (footprint "eagle-import:C0402")
      (libsource (lib "eagle-import") (part "C-USC0402"))
    )
    (comp (ref "C214")
      (value "C-USC0402")
      (footprint "eagle-import:C0402")
      (libsource (lib "eagle-import") (part "C-USC0402"))
    )
    (comp (ref "C215")
      (value "C-USC0402")
      (footprint "eagle-import:C0402")
      (libsource (lib "eagle-import") (part "C-USC0402"))
    )
    (comp (ref "C216")
      (value "C-USC0402")
      (footprint "eagle-import:C0402")
      (libsource (lib "eagle-import") (part "C-USC0402"))
    )
    (comp (ref "C217")
      (value "C-USC0402")
      (footprint "eagle-import:C0402")
      (libsource (lib "eagle-import") (part "C-USC0402"))
    )
    (comp (ref "C218")
      (value "C-USC0402")
      (footprint "eagle-import:C0402")
      (libsource (lib "eagle-import") (part "C-USC0402"))
    )
    (comp (ref "C219")
      (value "C-USC0402")
      (footprint "eagle-import:C0402")
      (libsource (lib "eagle-import") (part "C-USC0402"))
    )
    (comp (ref "C220")
      (value "C-USC0402")
      (footprint "eagle-import:C0402")
      (libsource (lib "eagle-import") (part "C-USC0402"))
    )
    (comp (ref "C221")
      (value "C-USC0402")
      (footprint "eagle-import:C0402")
      (libsource (lib "eagle-import") (part "C-USC0402"))
    )
    (comp (ref "C222")
      (value "C-USC0402")
      (footprint "eagle-import:C0402")
      (libsource (lib "eagle-import") (part "C-USC0402"))
    )
    (comp (ref "C223")
      (value "C-USC0402")
      (footprint "eagle-import:C0402")
      (libsource (lib "eagle-import") (part "C-USC0402"))
    )
    (comp (ref "C224")
      (value "C-USC0402")
      (footprint "eagle-import:C0402")
      (libsource (lib "eagle-import") (part "C-USC0402"))
    )
    (comp (ref "C225")
      (value "C-USC0402")
      (footprint "eagle-import:C0402")
      (libsource (lib "eagle-import") (part "C-USC0402"))
    )
    (comp (ref "C226")
      (value "C-USC0402")
      (footprint "eagle-import:C0402")
      (libsource (lib "eagle-import") (part "C-USC0402"))
    )
    (comp (ref "C227")
      (value "C-USC0402")
      (footprint "eagle-import:C0402")
      (libsource (lib "eagle-import") (part "C-USC0402"))
    )
    (comp (ref "C228")
      (value "C-USC0402")
      (footprint "eagle-import:C0402")
      (libsource (lib "eagle-import") (part "C-USC0402"))
    )
    (comp (ref "C229")
      (value "C-USC0402")
      (footprint "eagle-import:C0402")
      (libsource (lib "eagle-import") (part "C-USC0402"))
    )
    (comp (ref "C230")
      (value "C-USC0402")
      (footprint "eagle-import:C0402")
      (libsource (lib "eagle-import") (part "C-USC0402"))
    )
    (comp (ref "C231")
      (value "C-USC0402")
      (footprint "eagle-import:C0402")
      (libsource (lib "eagle-import") (part "C-USC0402"))
    )
    (comp (ref "C232")
      (value "C-USC0402")
      (footprint "eagle-import:C0402")
      (libsource (lib "eagle-import") (part "C-USC0402"))
    )
    (comp (ref "C233")
      (value "C-USC0402")
      (footprint "eagle-import:C0402")
      (libsource (lib "eagle-import") (part "C-USC0402"))
    )
    (comp (ref "C234")
      (value "C-USC0402")
      (footprint "eagle-import:C0402")
      (libsource (lib "eagle-import") (part "C-USC0402"))
    )
    (comp (ref "C235")
      (value "C-USC0402")
      (footprint "eagle-import:C0402")
      (libsource (lib "eagle-import") (part "C-USC0402"))
    )
    (comp (ref "C236")
      (value "C-USC0402")
      (footprint "eagle-import:C0402")
      (libsource (lib "eagle-import") (part "C-USC0402"))
    )
    (comp (ref "C237")
      (value "C-USC0402")
      (footprint "eagle-import:C0402")
      (libsource (lib "eagle-import") (part "C-USC0402"))
    )
    (comp (ref "C238")
      (value "C-USC0402")
      (footprint "eagle-import:C0402")
      (libsource (lib "eagle-import") (part "C-USC0402"))
    )
    (comp (ref "C239")
      (value "C-USC0402")
      (footprint "eagle-import:C0402")
      (libsource (lib "eagle-import") (part "C-USC0402"))
    )
    (comp (ref "C240")
      (value "C-USC0402")
      (footprint "eagle-import:C0402")
      (libsource (lib "eagle-import") (part "C-USC0402"))
    )
    (comp (ref "C241")
      (value "C-USC0402")
      (footprint "eagle-import:C0402")
      (libsource (lib "eagle-import") (part "C-USC0402"))
    )
    (comp (ref "C242")
      (value "C-USC0402")
      (footprint "eagle-import:C0402")
      (libsource (lib "eagle-import") (part "C-USC0402"))
    )
    (comp (ref "C243")
      (value "C-USC0402")
      (footprint "eagle-import:C0402")
      (libsource (lib "eagle-import") (part "C-USC0402"))
    )
    (comp (ref "C244")
      (value "C-USC0402")
      (footprint "eagle-import:C0402")
      (libsource (lib "eagle-import") (part "C-USC0402"))
    )
    (comp (ref "C245")
      (value "C-USC0402")
      (footprint "eagle-import:C0402")
      (libsource (lib "eagle-import") (part "C-USC0402"))
    )
    (comp (ref "C246")
      (value "C-USC0402")
      (footprint "eagle-import:C0402")
      (libsource (lib "eagle-import") (part "C-USC0402"))
    )
    (comp (ref "C247")
      (value "C-USC0402")
      (footprint "eagle-import:C0402")
      (libsource (lib "eagle-import") (part "C-USC0402"))
    )
    (comp (ref "C248")
      (value "C-USC0402")
      (footprint "eagle-import:C0402")
      (libsource (lib "eagle-import") (part "C-USC0402"))
    )
    (comp (ref "C249")
      (value "C-USC0402")
      (footprint "eagle-import:C0402")
      (libsource (lib "eagle-import") (part "C-USC0402"))
    )
    (comp (ref "C250")
      (value "C-USC0402")
      (footprint "eagle-import:C0402")
      (libsource (lib "eagle-import") (part "C-USC0402"))
    )
    (comp (ref "C251")
      (value "C-USC0402")
      (footprint "eagle-import:C0402")
      (libsource (lib "eagle-import") (part "C-USC0402"))
    )
    (comp (ref "C252")
      (value "C-USC0402")
      (footprint "eagle-import:C0402")
      (libsource (lib "eagle-import") (part "C-USC0402"))
    )
    (comp (ref "C253")
      (value "C-USC0402")
      (footprint "eagle-import:C0402")
      (libsource (lib "eagle-import") (part "C-USC0402"))
    )
    (comp (ref "C254")
      (value "C-USC0402")
      (footprint "eagle-import:C0402")
      (libsource (lib "eagle-import") (part "C-USC0402"))
    )
    (comp (ref "C255")
      (value "C-USC0402")
      (footprint "eagle-import:C0402")
      (libsource (lib "eagle-import") (part "C-USC0402"))
    )
    (comp (ref "C256")
      (value "C-USC0402")
      (footprint "eagle-import:C0402")
      (libsource (lib "eagle-import") (part "C-USC0402"))
    )
    (comp (ref "C257")
      (value "C-USC0402")
      (footprint "eagle-import:C0402")
      (libsource (lib "eagle-import") (part "C-USC0402"))
    )
    (comp (ref "C258")
      (value "C-USC0402")
      (footprint "eagle-import:C0402")
      (libsource (lib "eagle-import") (part "C-USC0402"))
    )
    (comp (ref "C259")
      (value "C-USC0402")
      (footprint "eagle-import:C0402")
      (libsource (lib "eagle-import") (part "C-USC0402"))
    )
    (comp (ref "C260")
      (value "C-USC0402")
      (footprint "eagle-import:C0402")
      (libsource (lib "eagle-import") (part "C-USC0402"))
    )
    (comp (ref "C261")
      (value "C-USC0402")
      (footprint "eagle-import:C0402")
      (libsource (lib "eagle-import") (part "C-USC0402"))
    )
    (comp (ref "C262")
      (value "C-USC0402")
      (footprint "eagle-import:C0402")
      (libsource (lib "eagle-import") (part "C-USC0402"))
    )
    (comp (ref "C263")
      (value "C-USC0402")
      (footprint "eagle-import:C0402")
      (libsource (lib "eagle-import") (part "C-USC0402"))
    )
    (comp (ref "C264")
      (value "C-USC0402")
      (footprint "eagle-import:C0402")
      (libsource (lib "eagle-import") (part "C-USC0402"))
    )
    (comp (ref "C265")
      (value "C-USC0402")
      (footprint "eagle-import:C0402")
      (libsource (lib "eagle-import") (part "C-USC0402"))
    )
    (comp (ref "C266")
      (value "C-USC0402")
      (footprint "eagle-import:C0402")
      (libsource (lib "eagle-import") (part "C-USC0402"))
    )
    (comp (ref "C267")
      (value "C-USC0402")
      (footprint "eagle-import:C0402")
      (libsource (lib "eagle-import") (part "C-USC0402"))
    )
    (comp (ref "C268")
      (value "C-USC0402")
      (footprint "eagle-import:C0402")
      (libsource (lib "eagle-import") (part "C-USC0402"))
    )
    (comp (ref "C269")
      (value "C-USC0402")
      (footprint "eagle-import:C0402")
      (libsource (lib "eagle-import") (part "C-USC0402"))
    )
    (comp (ref "C270")
      (value "C-USC0402")
      (footprint "eagle-import:C0402")
      (libsource (lib "eagle-import") (part "C-USC0402"))
    )
    (comp (ref "C271")
      (value "C-USC0402")
      (footprint "eagle-import:C0402")
      (libsource (lib "eagle-import") (part "C-USC0402"))
    )
    (comp (ref "C272")
      (value "C-USC0402")
      (footprint "eagle-import:C0402")
      (libsource (lib "eagle-import") (part "C-USC0402"))
    )
    (comp (ref "C273")
      (value "C-USC0402")
      (footprint "eagle-import:C0402")
      (libsource (lib "eagle-import") (part "C-USC0402"))
    )
    (comp (ref "C274")
      (value "C-USC0402")
      (footprint "eagle-import:C0402")
      (libsource (lib "eagle-import") (part "C-USC0402"))
    )
    (comp (ref "C275")
      (value "C-USC0402")
      (footprint "eagle-import:C0402")
      (libsource (lib "eagle-import") (part "C-USC0402"))
    )
    (comp (ref "C276")
      (value "C-USC0402")
      (footprint "eagle-import:C0402")
      (libsource (lib "eagle-import") (part "C-USC0402"))
    )
    (comp (ref "C277")
      (value "C-USC0402")
      (footprint "eagle-import:C0402")
      (libsource (lib "eagle-import") (part "C-USC0402"))
    )
    (comp (ref "C278")
      (value "C-USC0402")
      (footprint "eagle-import:C0402")
      (libsource (lib "eagle-import") (part "C-USC0402"))
    )
    (comp (ref "C279")
      (value "C-USC0402")
      (footprint "eagle-import:C0402")
      (libsource (lib "eagle-import") (part "C-USC0402"))
    )
    (comp (ref "C280")
      (value "C-USC0402")
      (footprint "eagle-import:C0402")
      (libsource (lib "eagle-import") (part "C-USC0402"))
    )
    (comp (ref "C281")
      (value "C-USC0402")
      (footprint "eagle-import:C0402")
      (libsource (lib "eagle-import") (part "C-USC0402"))
    )
    (comp (ref "C282")
      (value "C-USC0402")
      (footprint "eagle-import:C0402")
      (libsource (lib "eagle-import") (part "C-USC0402"))
    )
    (comp (ref "C283")
      (value "C-USC0402")
      (footprint "eagle-import:C0402")
      (libsource (lib "eagle-import") (part "C-USC0402"))
    )
    (comp (ref "C284")
      (value "C-USC0402")
      (footprint "eagle-import:C0402")
      (libsource (lib "eagle-import") (part "C-USC0402"))
    )
    (comp (ref "C285")
      (value "C-USC0402")
      (footprint "eagle-import:C0402")
      (libsource (lib "eagle-import") (part "C-USC0402"))
    )
    (comp (ref "C286")
      (value "C-USC0402")
      (footprint "eagle-import:C0402")
      (libsource (lib "eagle-import") (part "C-USC0402"))
    )
    (comp (ref "C287")
      (value "C-USC0402")
      (footprint "eagle-import:C0402")
      (libsource (lib "eagle-import") (part "C-USC0402"))
    )
    (comp (ref "C288")
      (value "C-USC0402")
      (footprint "eagle-import:C0402")
      (libsource (lib "eagle-import") (part "C-USC0402"))
    )
    (comp (ref "C289")
      (value "C-USC0402")
      (footprint "eagle-import:C0402")
      (libsource (lib "eagle-import") (part "C-USC0402"))
    )
    (comp (ref "C290")
      (value "C-USC0402")
      (footprint "eagle-import:C0402")
      (libsource (lib "eagle-import") (part "C-USC0402"))
    )
    (comp (ref "C291")
      (value "C-USC0402")
      (footprint "eagle-import:C0402")
      (libsource (lib "eagle-import") (part "C-USC0402"))
    )
    (comp (ref "C292")
      (value "C-USC0402")
      (footprint "eagle-import:C0402")
      (libsource (lib "eagle-import") (part "C-USC0402"))
    )
    (comp (ref "C293")
      (value "C-USC0402")
      (footprint "eagle-import:C0402")
      (libsource (lib "eagle-import") (part "C-USC0402"))
    )
    (comp (ref "C294")
      (value "C-USC0402")
      (footprint "eagle-import:C0402")
      (libsource (lib "eagle-import") (part "C-USC0402"))
    )
    (comp (ref "C295")
      (value "C-USC0402")
      (footprint "eagle-import:C0402")
      (libsource (lib "eagle-import") (part "C-USC0402"))
    )
    (comp (ref "C296")
      (value "C-USC0402")
      (footprint "eagle-import:C0402")
      (libsource (lib "eagle-import") (part "C-USC0402"))
    )
    (comp (ref "C297")
      (value "C-USC0402")
      (footprint "eagle-import:C0402")
      (libsource (lib "eagle-import") (part "C-USC0402"))
    )
    (comp (ref "C298")
      (value "C-USC0402")
      (footprint "eagle-import:C0402")
      (libsource (lib "eagle-import") (part "C-USC0402"))
    )
    (comp (ref "C299")
      (value "C-USC0402")
      (footprint "eagle-import:C0402")
      (libsource (lib "eagle-import") (part "C-USC0402"))
    )
    (comp (ref "C300")
      (value "C-USC0402")
      (footprint "eagle-import:C0402")
      (libsource (lib "eagle-import") (part "C-USC0402"))
    )
    (comp (ref "J1")
      (value "MOLEX_502598-5193MOLEX_502598-5193_0_0")
      (footprint "eagle-import:MOLEX_502598-5193_0")
      (fields (field (name "MF") "Molex") (field (name "MPN") "502598-5193"))
      (libsource (lib "eagle-import") (part "MOLEX_502598-5193MOLEX_502598-5193_0_0"))
    )
    (comp (ref "J2")
      (value "MOLEX_502598-5193MOLEX_502598-5193_0_0")
      (footprint "eagle-import:MOLEX_502598-5193_0")
      (fields (field (name "MF") "Molex") (field (name "MPN") "502598-5193"))
      (libsource (lib "eagle-import") (part "MOLEX_502598-5193MOLEX_502598-5193_0_0"))
    )
    (comp (ref "R1")
      (value "R-US_R0402")
      (footprint "eagle-import:R0402")
      (libsource (lib "eagle-import") (part "R-US_R0402"))
    )
    (comp (ref "R2")
      (value "R-US_R0402")
      (footprint "eagle-import:R0402")
      (libsource (lib "eagle-import") (part "R-US_R0402"))
    )
    (comp (ref "R3")
      (value "R-US_R0402")
      (footprint "eagle-import:R0402")
      (libsource (lib "eagle-import") (part "R-US_R0402"))
    )
    (comp (ref "R4")
      (value "R-US_R0402")
      (footprint "eagle-import:R0402")
      (libsource (lib "eagle-import") (part "R-US_R0402"))
    )
    (comp (ref "R5")
      (value "R-US_R0402")
      (footprint "eagle-import:R0402")
      (libsource (lib "eagle-import") (part "R-US_R0402"))
    )
    (comp (ref "R6")
      (value "R-US_R0402")
      (footprint "eagle-import:R0402")
      (libsource (lib "eagle-import") (part "R-US_R0402"))
    )
    (comp (ref "R7")
      (value "R-US_R0402")
      (footprint "eagle-import:R0402")
      (libsource (lib "eagle-import") (part "R-US_R0402"))
    )
    (comp (ref "R8")
      (value "R-US_R0402")
      (footprint "eagle-import:R0402")
      (libsource (lib "eagle-import") (part "R-US_R0402"))
    )
    (comp (ref "R9")
      (value "R-US_R0402")
      (footprint "eagle-import:R0402")
      (libsource (lib "eagle-import") (part "R-US_R0402"))
    )
    (comp (ref "R10")
      (value "R-US_R0402")
      (footprint "eagle-import:R0402")
      (libsource (lib "eagle-import") (part "R-US_R0402"))
    )
    (comp (ref "R11")
      (value "R-US_R0402")
      (footprint "eagle-import:R0402")
      (libsource (lib "eagle-import") (part "R-US_R0402"))
    )
    (comp (ref "R12")
      (value "R-US_R0402")
      (footprint "eagle-import:R0402")
      (libsource (lib "eagle-import") (part "R-US_R0402"))
    )
    (comp (ref "R13")
      (value "R-US_R0402")
      (footprint "eagle-import:R0402")
      (libsource (lib "eagle-import") (part "R-US_R0402"))
    )
    (comp (ref "R14")
      (value "R-US_R0402")
      (footprint "eagle-import:R0402")
      (libsource (lib "eagle-import") (part "R-US_R0402"))
    )
    (comp (ref "R15")
      (value "R-US_R0402")
      (footprint "eagle-import:R0402")
      (libsource (lib "eagle-import") (part "R-US_R0402"))
    )
    (comp (ref "R16")
      (value "R-US_R0402")
      (footprint "eagle-import:R0402")
      (libsource (lib "eagle-import") (part "R-US_R0402"))
    )
    (comp (ref "R17")
      (value "R-US_R0402")
      (footprint "eagle-import:R0402")
      (libsource (lib "eagle-import") (part "R-US_R0402"))
    )
    (comp (ref "R18")
      (value "R-US_R0402")
      (footprint "eagle-import:R0402")
      (libsource (lib "eagle-import") (part "R-US_R0402"))
    )
    (comp (ref "R19")
      (value "R-US_R0402")
      (footprint "eagle-import:R0402")
      (libsource (lib "eagle-import") (part "R-US_R0402"))
    )
    (comp (ref "R20")
      (value "R-US_R0402")
      (footprint "eagle-import:R0402")
      (libsource (lib "eagle-import") (part "R-US_R0402"))
    )
    (comp (ref "R21")
      (value "R-US_R0402")
      (footprint "eagle-import:R0402")
      (libsource (lib "eagle-import") (part "R-US_R0402"))
    )
    (comp (ref "R22")
      (value "R-US_R0402")
      (footprint "eagle-import:R0402")
      (libsource (lib "eagle-import") (part "R-US_R0402"))
    )
    (comp (ref "R23")
      (value "R-US_R0402")
      (footprint "eagle-import:R0402")
      (libsource (lib "eagle-import") (part "R-US_R0402"))
    )
    (comp (ref "R24")
      (value "R-US_R0402")
      (footprint "eagle-import:R0402")
      (libsource (lib "eagle-import") (part "R-US_R0402"))
    )
    (comp (ref "R25")
      (value "R-US_R0402")
      (footprint "eagle-import:R0402")
      (libsource (lib "eagle-import") (part "R-US_R0402"))
    )
    (comp (ref "R26")
      (value "R-US_R0402")
      (footprint "eagle-import:R0402")
      (libsource (lib "eagle-import") (part "R-US_R0402"))
    )
    (comp (ref "R27")
      (value "R-US_R0402")
      (footprint "eagle-import:R0402")
      (libsource (lib "eagle-import") (part "R-US_R0402"))
    )
    (comp (ref "R28")
      (value "R-US_R0402")
      (footprint "eagle-import:R0402")
      (libsource (lib "eagle-import") (part "R-US_R0402"))
    )
    (comp (ref "R29")
      (value "R-US_R0402")
      (footprint "eagle-import:R0402")
      (libsource (lib "eagle-import") (part "R-US_R0402"))
    )
    (comp (ref "R30")
      (value "R-US_R0402")
      (footprint "eagle-import:R0402")
      (libsource (lib "eagle-import") (part "R-US_R0402"))
    )
    (comp (ref "R31")
      (value "R-US_R0402")
      (footprint "eagle-import:R0402")
      (libsource (lib "eagle-import") (part "R-US_R0402"))
    )
    (comp (ref "R32")
      (value "R-US_R0402")
      (footprint "eagle-import:R0402")
      (libsource (lib "eagle-import") (part "R-US_R0402"))
    )
    (comp (ref "R33")
      (value "R-US_R0402")
      (footprint "eagle-import:R0402")
      (libsource (lib "eagle-import") (part "R-US_R0402"))
    )
    (comp (ref "R34")
      (value "R-US_R0402")
      (footprint "eagle-import:R0402")
      (libsource (lib "eagle-import") (part "R-US_R0402"))
    )
    (comp (ref "R35")
      (value "R-US_R0402")
      (footprint "eagle-import:R0402")
      (libsource (lib "eagle-import") (part "R-US_R0402"))
    )
    (comp (ref "R36")
      (value "R-US_R0402")
      (footprint "eagle-import:R0402")
      (libsource (lib "eagle-import") (part "R-US_R0402"))
    )
    (comp (ref "R37")
      (value "R-US_R0402")
      (footprint "eagle-import:R0402")
      (libsource (lib "eagle-import") (part "R-US_R0402"))
    )
    (comp (ref "R38")
      (value "R-US_R0402")
      (footprint "eagle-import:R0402")
      (libsource (lib "eagle-import") (part "R-US_R0402"))
    )
    (comp (ref "R39")
      (value "R-US_R0402")
      (footprint "eagle-import:R0402")
      (libsource (lib "eagle-import") (part "R-US_R0402"))
    )
    (comp (ref "R40")
      (value "R-US_R0402")
      (footprint "eagle-import:R0402")
      (libsource (lib "eagle-import") (part "R-US_R0402"))
    )
    (comp (ref "R41")
      (value "R-US_R0402")
      (footprint "eagle-import:R0402")
      (libsource (lib "eagle-import") (part "R-US_R0402"))
    )
    (comp (ref "R42")
      (value "R-US_R0402")
      (footprint "eagle-import:R0402")
      (libsource (lib "eagle-import") (part "R-US_R0402"))
    )
    (comp (ref "R43")
      (value "R-US_R0402")
      (footprint "eagle-import:R0402")
      (libsource (lib "eagle-import") (part "R-US_R0402"))
    )
    (comp (ref "R44")
      (value "R-US_R0402")
      (footprint "eagle-import:R0402")
      (libsource (lib "eagle-import") (part "R-US_R0402"))
    )
    (comp (ref "R45")
      (value "R-US_R0402")
      (footprint "eagle-import:R0402")
      (libsource (lib "eagle-import") (part "R-US_R0402"))
    )
    (comp (ref "R46")
      (value "R-US_R0402")
      (footprint "eagle-import:R0402")
      (libsource (lib "eagle-import") (part "R-US_R0402"))
    )
    (comp (ref "R47")
      (value "R-US_R0402")
      (footprint "eagle-import:R0402")
      (libsource (lib "eagle-import") (part "R-US_R0402"))
    )
    (comp (ref "R48")
      (value "R-US_R0402")
      (footprint "eagle-import:R0402")
      (libsource (lib "eagle-import") (part "R-US_R0402"))
    )
    (comp (ref "R49")
      (value "R-US_R0402")
      (footprint "eagle-import:R0402")
      (libsource (lib "eagle-import") (part "R-US_R0402"))
    )
    (comp (ref "R50")
      (value "R-US_R0402")
      (footprint "eagle-import:R0402")
      (libsource (lib "eagle-import") (part "R-US_R0402"))
    )
    (comp (ref "R51")
      (value "R-US_R0402")
      (footprint "eagle-import:R0402")
      (libsource (lib "eagle-import") (part "R-US_R0402"))
    )
    (comp (ref "R52")
      (value "R-US_R0402")
      (footprint "eagle-import:R0402")
      (libsource (lib "eagle-import") (part "R-US_R0402"))
    )
    (comp (ref "R53")
      (value "R-US_R0402")
      (footprint "eagle-import:R0402")
      (libsource (lib "eagle-import") (part "R-US_R0402"))
    )
    (comp (ref "R54")
      (value "R-US_R0402")
      (footprint "eagle-import:R0402")
      (libsource (lib "eagle-import") (part "R-US_R0402"))
    )
    (comp (ref "R55")
      (value "R-US_R0402")
      (footprint "eagle-import:R0402")
      (libsource (lib "eagle-import") (part "R-US_R0402"))
    )
    (comp (ref "R56")
      (value "R-US_R0402")
      (footprint "eagle-import:R0402")
      (libsource (lib "eagle-import") (part "R-US_R0402"))
    )
    (comp (ref "R57")
      (value "R-US_R0402")
      (footprint "eagle-import:R0402")
      (libsource (lib "eagle-import") (part "R-US_R0402"))
    )
    (comp (ref "R58")
      (value "R-US_R0402")
      (footprint "eagle-import:R0402")
      (libsource (lib "eagle-import") (part "R-US_R0402"))
    )
    (comp (ref "R59")
      (value "R-US_R0402")
      (footprint "eagle-import:R0402")
      (libsource (lib "eagle-import") (part "R-US_R0402"))
    )
    (comp (ref "R60")
      (value "R-US_R0402")
      (footprint "eagle-import:R0402")
      (libsource (lib "eagle-import") (part "R-US_R0402"))
    )
    (comp (ref "R61")
      (value "R-US_R0402")
      (footprint "eagle-import:R0402")
      (libsource (lib "eagle-import") (part "R-US_R0402"))
    )
    (comp (ref "R62")
      (value "R-US_R0402")
      (footprint "eagle-import:R0402")
      (libsource (lib "eagle-import") (part "R-US_R0402"))
    )
    (comp (ref "R63")
      (value "R-US_R0402")
      (footprint "eagle-import:R0402")
      (libsource (lib "eagle-import") (part "R-US_R0402"))
    )
    (comp (ref "R64")
      (value "R-US_R0402")
      (footprint "eagle-import:R0402")
      (libsource (lib "eagle-import") (part "R-US_R0402"))
    )
    (comp (ref "R65")
      (value "R-US_R0402")
      (footprint "eagle-import:R0402")
      (libsource (lib "eagle-import") (part "R-US_R0402"))
    )
    (comp (ref "R66")
      (value "R-US_R0402")
      (footprint "eagle-import:R0402")
      (libsource (lib "eagle-import") (part "R-US_R0402"))
    )
    (comp (ref "R67")
      (value "R-US_R0402")
      (footprint "eagle-import:R0402")
      (libsource (lib "eagle-import") (part "R-US_R0402"))
    )
    (comp (ref "R68")
      (value "R-US_R0402")
      (footprint "eagle-import:R0402")
      (libsource (lib "eagle-import") (part "R-US_R0402"))
    )
    (comp (ref "R69")
      (value "R-US_R0402")
      (footprint "eagle-import:R0402")
      (libsource (lib "eagle-import") (part "R-US_R0402"))
    )
    (comp (ref "R70")
      (value "R-US_R0402")
      (footprint "eagle-import:R0402")
      (libsource (lib "eagle-import") (part "R-US_R0402"))
    )
    (comp (ref "R71")
      (value "R-US_R0402")
      (footprint "eagle-import:R0402")
      (libsource (lib "eagle-import") (part "R-US_R0402"))
    )
    (comp (ref "R72")
      (value "R-US_R0402")
      (footprint "eagle-import:R0402")
      (libsource (lib "eagle-import") (part "R-US_R0402"))
    )
    (comp (ref "R73")
      (value "R-US_R0402")
      (footprint "eagle-import:R0402")
      (libsource (lib "eagle-import") (part "R-US_R0402"))
    )
    (comp (ref "R74")
      (value "R-US_R0402")
      (footprint "eagle-import:R0402")
      (libsource (lib "eagle-import") (part "R-US_R0402"))
    )
    (comp (ref "R75")
      (value "R-US_R0402")
      (footprint "eagle-import:R0402")
      (libsource (lib "eagle-import") (part "R-US_R0402"))
    )
    (comp (ref "R76")
      (value "R-US_R0402")
      (footprint "eagle-import:R0402")
      (libsource (lib "eagle-import") (part "R-US_R0402"))
    )
    (comp (ref "R77")
      (value "R-US_R0402")
      (footprint "eagle-import:R0402")
      (libsource (lib "eagle-import") (part "R-US_R0402"))
    )
    (comp (ref "R78")
      (value "R-US_R0402")
      (footprint "eagle-import:R0402")
      (libsource (lib "eagle-import") (part "R-US_R0402"))
    )
    (comp (ref "R79")
      (value "R-US_R0402")
      (footprint "eagle-import:R0402")
      (libsource (lib "eagle-import") (part "R-US_R0402"))
    )
    (comp (ref "R80")
      (value "R-US_R0402")
      (footprint "eagle-import:R0402")
      (libsource (lib "eagle-import") (part "R-US_R0402"))
    )
    (comp (ref "R81")
      (value "R-US_R0402")
      (footprint "eagle-import:R0402")
      (libsource (lib "eagle-import") (part "R-US_R0402"))
    )
    (comp (ref "R82")
      (value "R-US_R0402")
      (footprint "eagle-import:R0402")
      (libsource (lib "eagle-import") (part "R-US_R0402"))
    )
    (comp (ref "R83")
      (value "R-US_R0402")
      (footprint "eagle-import:R0402")
      (libsource (lib "eagle-import") (part "R-US_R0402"))
    )
    (comp (ref "R84")
      (value "R-US_R0402")
      (footprint "eagle-import:R0402")
      (libsource (lib "eagle-import") (part "R-US_R0402"))
    )
    (comp (ref "R85")
      (value "R-US_R0402")
      (footprint "eagle-import:R0402")
      (libsource (lib "eagle-import") (part "R-US_R0402"))
    )
    (comp (ref "R86")
      (value "R-US_R0402")
      (footprint "eagle-import:R0402")
      (libsource (lib "eagle-import") (part "R-US_R0402"))
    )
    (comp (ref "R87")
      (value "R-US_R0402")
      (footprint "eagle-import:R0402")
      (libsource (lib "eagle-import") (part "R-US_R0402"))
    )
    (comp (ref "R88")
      (value "R-US_R0402")
      (footprint "eagle-import:R0402")
      (libsource (lib "eagle-import") (part "R-US_R0402"))
    )
    (comp (ref "R89")
      (value "R-US_R0402")
      (footprint "eagle-import:R0402")
      (libsource (lib "eagle-import") (part "R-US_R0402"))
    )
    (comp (ref "R90")
      (value "R-US_R0402")
      (footprint "eagle-import:R0402")
      (libsource (lib "eagle-import") (part "R-US_R0402"))
    )
    (comp (ref "R91")
      (value "R-US_R0402")
      (footprint "eagle-import:R0402")
      (libsource (lib "eagle-import") (part "R-US_R0402"))
    )
    (comp (ref "R92")
      (value "R-US_R0402")
      (footprint "eagle-import:R0402")
      (libsource (lib "eagle-import") (part "R-US_R0402"))
    )
    (comp (ref "R93")
      (value "R-US_R0402")
      (footprint "eagle-import:R0402")
      (libsource (lib "eagle-import") (part "R-US_R0402"))
    )
    (comp (ref "R94")
      (value "R-US_R0402")
      (footprint "eagle-import:R0402")
      (libsource (lib "eagle-import") (part "R-US_R0402"))
    )
    (comp (ref "R95")
      (value "R-US_R0402")
      (footprint "eagle-import:R0402")
      (libsource (lib "eagle-import") (part "R-US_R0402"))
    )
    (comp (ref "R96")
      (value "R-US_R0402")
      (footprint "eagle-import:R0402")
      (libsource (lib "eagle-import") (part "R-US_R0402"))
    )
    (comp (ref "R97")
      (value "R-US_R0402")
      (footprint "eagle-import:R0402")
      (libsource (lib "eagle-import") (part "R-US_R0402"))
    )
    (comp (ref "R98")
      (value "R-US_R0402")
      (footprint "eagle-import:R0402")
      (libsource (lib "eagle-import") (part "R-US_R0402"))
    )
    (comp (ref "R99")
      (value "R-US_R0402")
      (footprint "eagle-import:R0402")
      (libsource (lib "eagle-import") (part "R-US_R0402"))
    )
    (comp (ref "R100")
      (value "R-US_R0402")
      (footprint "eagle-import:R0402")
      (libsource (lib "eagle-import") (part "R-US_R0402"))
    )
    (comp (ref "R101")
      (value "R-US_R0402")
      (footprint "eagle-import:R0402")
      (libsource (lib "eagle-import") (part "R-US_R0402"))
    )
    (comp (ref "R102")
      (value "R-US_R0402")
      (footprint "eagle-import:R0402")
      (libsource (lib "eagle-import") (part "R-US_R0402"))
    )
    (comp (ref "R103")
      (value "R-US_R0402")
      (footprint "eagle-import:R0402")
      (libsource (lib "eagle-import") (part "R-US_R0402"))
    )
    (comp (ref "R104")
      (value "R-US_R0402")
      (footprint "eagle-import:R0402")
      (libsource (lib "eagle-import") (part "R-US_R0402"))
    )
    (comp (ref "R105")
      (value "R-US_R0402")
      (footprint "eagle-import:R0402")
      (libsource (lib "eagle-import") (part "R-US_R0402"))
    )
    (comp (ref "R106")
      (value "R-US_R0402")
      (footprint "eagle-import:R0402")
      (libsource (lib "eagle-import") (part "R-US_R0402"))
    )
    (comp (ref "R107")
      (value "R-US_R0402")
      (footprint "eagle-import:R0402")
      (libsource (lib "eagle-import") (part "R-US_R0402"))
    )
    (comp (ref "R108")
      (value "R-US_R0402")
      (footprint "eagle-import:R0402")
      (libsource (lib "eagle-import") (part "R-US_R0402"))
    )
    (comp (ref "R109")
      (value "R-US_R0402")
      (footprint "eagle-import:R0402")
      (libsource (lib "eagle-import") (part "R-US_R0402"))
    )
    (comp (ref "R110")
      (value "R-US_R0402")
      (footprint "eagle-import:R0402")
      (libsource (lib "eagle-import") (part "R-US_R0402"))
    )
    (comp (ref "R111")
      (value "R-US_R0402")
      (footprint "eagle-import:R0402")
      (libsource (lib "eagle-import") (part "R-US_R0402"))
    )
    (comp (ref "R112")
      (value "R-US_R0402")
      (footprint "eagle-import:R0402")
      (libsource (lib "eagle-import") (part "R-US_R0402"))
    )
    (comp (ref "R113")
      (value "R-US_R0402")
      (footprint "eagle-import:R0402")
      (libsource (lib "eagle-import") (part "R-US_R0402"))
    )
    (comp (ref "R114")
      (value "R-US_R0402")
      (footprint "eagle-import:R0402")
      (libsource (lib "eagle-import") (part "R-US_R0402"))
    )
    (comp (ref "R115")
      (value "R-US_R0402")
      (footprint "eagle-import:R0402")
      (libsource (lib "eagle-import") (part "R-US_R0402"))
    )
    (comp (ref "R116")
      (value "R-US_R0402")
      (footprint "eagle-import:R0402")
      (libsource (lib "eagle-import") (part "R-US_R0402"))
    )
    (comp (ref "R117")
      (value "R-US_R0402")
      (footprint "eagle-import:R0402")
      (libsource (lib "eagle-import") (part "R-US_R0402"))
    )
    (comp (ref "R118")
      (value "R-US_R0402")
      (footprint "eagle-import:R0402")
      (libsource (lib "eagle-import") (part "R-US_R0402"))
    )
    (comp (ref "R119")
      (value "R-US_R0402")
      (footprint "eagle-import:R0402")
      (libsource (lib "eagle-import") (part "R-US_R0402"))
    )
    (comp (ref "R120")
      (value "R-US_R0402")
      (footprint "eagle-import:R0402")
      (libsource (lib "eagle-import") (part "R-US_R0402"))
    )
    (comp (ref "R121")
      (value "R-US_R0402")
      (footprint "eagle-import:R0402")
      (libsource (lib "eagle-import") (part "R-US_R0402"))
    )
    (comp (ref "R122")
      (value "R-US_R0402")
      (footprint "eagle-import:R0402")
      (libsource (lib "eagle-import") (part "R-US_R0402"))
    )
    (comp (ref "R123")
      (value "R-US_R0402")
      (footprint "eagle-import:R0402")
      (libsource (lib "eagle-import") (part "R-US_R0402"))
    )
    (comp (ref "R124")
      (value "R-US_R0402")
      (footprint "eagle-import:R0402")
      (libsource (lib "eagle-import") (part "R-US_R0402"))
    )
    (comp (ref "R125")
      (value "R-US_R0402")
      (footprint "eagle-import:R0402")
      (libsource (lib "eagle-import") (part "R-US_R0402"))
    )
    (comp (ref "R126")
      (value "R-US_R0402")
      (footprint "eagle-import:R0402")
      (libsource (lib "eagle-import") (part "R-US_R0402"))
    )
    (comp (ref "R127")
      (value "R-US_R0402")
      (footprint "eagle-import:R0402")
      (libsource (lib "eagle-import") (part "R-US_R0402"))
    )
    (comp (ref "R128")
      (value "R-US_R0402")
      (footprint "eagle-import:R0402")
      (libsource (lib "eagle-import") (part "R-US_R0402"))
    )
    (comp (ref "R129")
      (value "R-US_R0402")
      (footprint "eagle-import:R0402")
      (libsource (lib "eagle-import") (part "R-US_R0402"))
    )
    (comp (ref "R130")
      (value "R-US_R0402")
      (footprint "eagle-import:R0402")
      (libsource (lib "eagle-import") (part "R-US_R0402"))
    )
    (comp (ref "R131")
      (value "R-US_R0402")
      (footprint "eagle-import:R0402")
      (libsource (lib "eagle-import") (part "R-US_R0402"))
    )
    (comp (ref "R132")
      (value "R-US_R0402")
      (footprint "eagle-import:R0402")
      (libsource (lib "eagle-import") (part "R-US_R0402"))
    )
    (comp (ref "R133")
      (value "R-US_R0402")
      (footprint "eagle-import:R0402")
      (libsource (lib "eagle-import") (part "R-US_R0402"))
    )
    (comp (ref "R134")
      (value "R-US_R0402")
      (footprint "eagle-import:R0402")
      (libsource (lib "eagle-import") (part "R-US_R0402"))
    )
    (comp (ref "R135")
      (value "R-US_R0402")
      (footprint "eagle-import:R0402")
      (libsource (lib "eagle-import") (part "R-US_R0402"))
    )
    (comp (ref "R136")
      (value "R-US_R0402")
      (footprint "eagle-import:R0402")
      (libsource (lib "eagle-import") (part "R-US_R0402"))
    )
    (comp (ref "R137")
      (value "R-US_R0402")
      (footprint "eagle-import:R0402")
      (libsource (lib "eagle-import") (part "R-US_R0402"))
    )
    (comp (ref "R138")
      (value "R-US_R0402")
      (footprint "eagle-import:R0402")
      (libsource (lib "eagle-import") (part "R-US_R0402"))
    )
    (comp (ref "R139")
      (value "R-US_R0402")
      (footprint "eagle-import:R0402")
      (libsource (lib "eagle-import") (part "R-US_R0402"))
    )
    (comp (ref "R140")
      (value "R-US_R0402")
      (footprint "eagle-import:R0402")
      (libsource (lib "eagle-import") (part "R-US_R0402"))
    )
    (comp (ref "R141")
      (value "R-US_R0402")
      (footprint "eagle-import:R0402")
      (libsource (lib "eagle-import") (part "R-US_R0402"))
    )
    (comp (ref "R142")
      (value "R-US_R0402")
      (footprint "eagle-import:R0402")
      (libsource (lib "eagle-import") (part "R-US_R0402"))
    )
    (comp (ref "R143")
      (value "R-US_R0402")
      (footprint "eagle-import:R0402")
      (libsource (lib "eagle-import") (part "R-US_R0402"))
    )
    (comp (ref "R144")
      (value "R-US_R0402")
      (footprint "eagle-import:R0402")
      (libsource (lib "eagle-import") (part "R-US_R0402"))
    )
    (comp (ref "R145")
      (value "R-US_R0402")
      (footprint "eagle-import:R0402")
      (libsource (lib "eagle-import") (part "R-US_R0402"))
    )
    (comp (ref "R146")
      (value "R-US_R0402")
      (footprint "eagle-import:R0402")
      (libsource (lib "eagle-import") (part "R-US_R0402"))
    )
    (comp (ref "R147")
      (value "R-US_R0402")
      (footprint "eagle-import:R0402")
      (libsource (lib "eagle-import") (part "R-US_R0402"))
    )
    (comp (ref "R148")
      (value "R-US_R0402")
      (footprint "eagle-import:R0402")
      (libsource (lib "eagle-import") (part "R-US_R0402"))
    )
    (comp (ref "R149")
      (value "R-US_R0402")
      (footprint "eagle-import:R0402")
      (libsource (lib "eagle-import") (part "R-US_R0402"))
    )
    (comp (ref "R150")
      (value "R-US_R0402")
      (footprint "eagle-import:R0402")
      (libsource (lib "eagle-import") (part "R-US_R0402"))
    )
  )
  (nets
    (net (code "1") (name "/GND") (class "Default")
      (node (ref "C1") (pin "2") (pinfunction "2_2") (pintype "passive"))
      (node (ref "C10") (pin "2") (pinfunction "2_2") (pintype "passive"))
      (node (ref "C100") (pin "2") (pinfunction "2_2") (pintype "passive"))
      (node (ref "C101") (pin "2") (pinfunction "2_2") (pintype "passive"))
      (node (ref "C102") (pin "2") (pinfunction "2_2") (pintype "passive"))
      (node (ref "C103") (pin "2") (pinfunction "2_2") (pintype "passive"))
      (node (ref "C104") (pin "2") (pinfunction "2_2") (pintype "passive"))
      (node (ref "C105") (pin "2") (pinfunction "2_2") (pintype "passive"))
      (node (ref "C106") (pin "2") (pinfunction "2_2") (pintype "passive"))
      (node (ref "C107") (pin "2") (pinfunction "2_2") (pintype "passive"))
      (node (ref "C108") (pin "2") (pinfunction "2_2") (pintype "passive"))
      (node (ref "C109") (pin "2") (pinfunction "2_2") (pintype "passive"))
      (node (ref "C11") (pin "2") (pinfunction "2_2") (pintype "passive"))
      (node (ref "C110") (pin "2") (pinfunction "2_2") (pintype "passive"))
      (node (ref "C111") (pin "2") (pinfunction "2_2") (pintype "passive"))
      (node (ref "C112") (pin "2") (pinfunction "2_2") (pintype "passive"))
      (node (ref "C113") (pin "2") (pinfunction "2_2") (pintype "passive"))
      (node (ref "C114") (pin "2") (pinfunction "2_2") (pintype "passive"))
      (node (ref "C115") (pin "2") (pinfunction "2_2") (pintype "passive"))
      (node (ref "C116") (pin "2") (pinfunction "2_2") (pintype "passive"))
      (node (ref "C117") (pin "2") (pinfunction "2_2") (pintype "passive"))
      (node (ref "C118") (pin "2") (pinfunction "2_2") (pintype "passive"))
      (node (ref "C119") (pin "2") (pinfunction "2_2") (pintype "passive"))
      (node (ref "C12") (pin "2") (pinfunction "2_2") (pintype "passive"))
      (node (ref "C120") (pin "2") (pinfunction "2_2") (pintype "passive"))
      (node (ref "C121") (pin "2") (pinfunction "2_2") (pintype "passive"))
      (node (ref "C122") (pin "2") (pinfunction "2_2") (pintype "passive"))
      (node (ref "C123") (pin "2") (pinfunction "2_2") (pintype "passive"))
      (node (ref "C124") (pin "2") (pinfunction "2_2") (pintype "passive"))
      (node (ref "C125") (pin "2") (pinfunction "2_2") (pintype "passive"))
      (node (ref "C126") (pin "2") (pinfunction "2_2") (pintype "passive"))
      (node (ref "C127") (pin "2") (pinfunction "2_2") (pintype "passive"))
      (node (ref "C128") (pin "2") (pinfunction "2_2") (pintype "passive"))
      (node (ref "C129") (pin "2") (pinfunction "2_2") (pintype "passive"))
      (node (ref "C13") (pin "2") (pinfunction "2_2") (pintype "passive"))
      (node (ref "C130") (pin "2") (pinfunction "2_2") (pintype "passive"))
      (node (ref "C131") (pin "2") (pinfunction "2_2") (pintype "passive"))
      (node (ref "C132") (pin "2") (pinfunction "2_2") (pintype "passive"))
      (node (ref "C133") (pin "2") (pinfunction "2_2") (pintype "passive"))
      (node (ref "C134") (pin "2") (pinfunction "2_2") (pintype "passive"))
      (node (ref "C135") (pin "2") (pinfunction "2_2") (pintype "passive"))
      (node (ref "C136") (pin "2") (pinfunction "2_2") (pintype "passive"))
      (node (ref "C137") (pin "2") (pinfunction "2_2") (pintype "passive"))
      (node (ref "C138") (pin "2") (pinfunction "2_2") (pintype "passive"))
      (node (ref "C139") (pin "2") (pinfunction "2_2") (pintype "passive"))
      (node (ref "C14") (pin "2") (pinfunction "2_2") (pintype "passive"))
      (node (ref "C140") (pin "2") (pinfunction "2_2") (pintype "passive"))
      (node (ref "C141") (pin "2") (pinfunction "2_2") (pintype "passive"))
      (node (ref "C142") (pin "2") (pinfunction "2_2") (pintype "passive"))
      (node (ref "C143") (pin "2") (pinfunction "2_2") (pintype "passive"))
      (node (ref "C144") (pin "2") (pinfunction "2_2") (pintype "passive"))
      (node (ref "C145") (pin "2") (pinfunction "2_2") (pintype "passive"))
      (node (ref "C146") (pin "2") (pinfunction "2_2") (pintype "passive"))
      (node (ref "C147") (pin "2") (pinfunction "2_2") (pintype "passive"))
      (node (ref "C148") (pin "2") (pinfunction "2_2") (pintype "passive"))
      (node (ref "C149") (pin "2") (pinfunction "2_2") (pintype "passive"))
      (node (ref "C15") (pin "2") (pinfunction "2_2") (pintype "passive"))
      (node (ref "C150") (pin "2") (pinfunction "2_2") (pintype "passive"))
      (node (ref "C151") (pin "2") (pinfunction "2_2") (pintype "passive"))
      (node (ref "C152") (pin "2") (pinfunction "2_2") (pintype "passive"))
      (node (ref "C153") (pin "2") (pinfunction "2_2") (pintype "passive"))
      (node (ref "C154") (pin "2") (pinfunction "2_2") (pintype "passive"))
      (node (ref "C155") (pin "2") (pinfunction "2_2") (pintype "passive"))
      (node (ref "C156") (pin "2") (pinfunction "2_2") (pintype "passive"))
      (node (ref "C157") (pin "2") (pinfunction "2_2") (pintype "passive"))
      (node (ref "C158") (pin "2") (pinfunction "2_2") (pintype "passive"))
      (node (ref "C159") (pin "2") (pinfunction "2_2") (pintype "passive"))
      (node (ref "C16") (pin "2") (pinfunction "2_2") (pintype "passive"))
      (node (ref "C160") (pin "2") (pinfunction "2_2") (pintype "passive"))
      (node (ref "C161") (pin "2") (pinfunction "2_2") (pintype "passive"))
      (node (ref "C162") (pin "2") (pinfunction "2_2") (pintype "passive"))
      (node (ref "C163") (pin "2") (pinfunction "2_2") (pintype "passive"))
      (node (ref "C164") (pin "2") (pinfunction "2_2") (pintype "passive"))
      (node (ref "C165") (pin "2") (pinfunction "2_2") (pintype "passive"))
      (node (ref "C166") (pin "2") (pinfunction "2_2") (pintype "passive"))
      (node (ref "C167") (pin "2") (pinfunction "2_2") (pintype "passive"))
      (node (ref "C168") (pin "2") (pinfunction "2_2") (pintype "passive"))
      (node (ref "C169") (pin "2") (pinfunction "2_2") (pintype "passive"))
      (node (ref "C17") (pin "2") (pinfunction "2_2") (pintype "passive"))
      (node (ref "C170") (pin "2") (pinfunction "2_2") (pintype "passive"))
      (node (ref "C171") (pin "2") (pinfunction "2_2") (pintype "passive"))
      (node (ref "C172") (pin "2") (pinfunction "2_2") (pintype "passive"))
      (node (ref "C173") (pin "2") (pinfunction "2_2") (pintype "passive"))
      (node (ref "C174") (pin "2") (pinfunction "2_2") (pintype "passive"))
      (node (ref "C175") (pin "2") (pinfunction "2_2") (pintype "passive"))
      (node (ref "C176") (pin "2") (pinfunction "2_2") (pintype "passive"))
      (node (ref "C177") (pin "2") (pinfunction "2_2") (pintype "passive"))
      (node (ref "C178") (pin "2") (pinfunction "2_2") (pintype "passive"))
      (node (ref "C179") (pin "2") (pinfunction "2_2") (pintype "passive"))
      (node (ref "C18") (pin "2") (pinfunction "2_2") (pintype "passive"))
      (node (ref "C180") (pin "2") (pinfunction "2_2") (pintype "passive"))
      (node (ref "C181") (pin "2") (pinfunction "2_2") (pintype "passive"))
      (node (ref "C182") (pin "2") (pinfunction "2_2") (pintype "passive"))
      (node (ref "C183") (pin "2") (pinfunction "2_2") (pintype "passive"))
      (node (ref "C184") (pin "2") (pinfunction "2_2") (pintype "passive"))
      (node (ref "C185") (pin "2") (pinfunction "2_2") (pintype "passive"))
      (node (ref "C186") (pin "2") (pinfunction "2_2") (pintype "passive"))
      (node (ref "C187") (pin "2") (pinfunction "2_2") (pintype "passive"))
      (node (ref "C188") (pin "2") (pinfunction "2_2") (pintype "passive"))
      (node (ref "C189") (pin "2") (pinfunction "2_2") (pintype "passive"))
      (node (ref "C19") (pin "2") (pinfunction "2_2") (pintype "passive"))
      (node (ref "C190") (pin "2") (pinfunction "2_2") (pintype "passive"))
      (node (ref "C191") (pin "2") (pinfunction "2_2") (pintype "passive"))
      (node (ref "C192") (pin "2") (pinfunction "2_2") (pintype "passive"))
      (node (ref "C193") (pin "2") (pinfunction "2_2") (pintype "passive"))
      (node (ref "C194") (pin "2") (pinfunction "2_2") (pintype "passive"))
      (node (ref "C195") (pin "2") (pinfunction "2_2") (pintype "passive"))
      (node (ref "C196") (pin "2") (pinfunction "2_2") (pintype "passive"))
      (node (ref "C197") (pin "2") (pinfunction "2_2") (pintype "passive"))
      (node (ref "C198") (pin "2") (pinfunction "2_2") (pintype "passive"))
      (node (ref "C199") (pin "2") (pinfunction "2_2") (pintype "passive"))
      (node (ref "C2") (pin "2") (pinfunction "2_2") (pintype "passive"))
      (node (ref "C20") (pin "2") (pinfunction "2_2") (pintype "passive"))
      (node (ref "C200") (pin "2") (pinfunction "2_2") (pintype "passive"))
      (node (ref "C201") (pin "2") (pinfunction "2_2") (pintype "passive"))
      (node (ref "C202") (pin "2") (pinfunction "2_2") (pintype "passive"))
      (node (ref "C203") (pin "2") (pinfunction "2_2") (pintype "passive"))
      (node (ref "C204") (pin "2") (pinfunction "2_2") (pintype "passive"))
      (node (ref "C205") (pin "2") (pinfunction "2_2") (pintype "passive"))
      (node (ref "C206") (pin "2") (pinfunction "2_2") (pintype "passive"))
      (node (ref "C207") (pin "2") (pinfunction "2_2") (pintype "passive"))
      (node (ref "C208") (pin "2") (pinfunction "2_2") (pintype "passive"))
      (node (ref "C209") (pin "2") (pinfunction "2_2") (pintype "passive"))
      (node (ref "C21") (pin "2") (pinfunction "2_2") (pintype "passive"))
      (node (ref "C210") (pin "2") (pinfunction "2_2") (pintype "passive"))
      (node (ref "C211") (pin "2") (pinfunction "2_2") (pintype "passive"))
      (node (ref "C212") (pin "2") (pinfunction "2_2") (pintype "passive"))
      (node (ref "C213") (pin "2") (pinfunction "2_2") (pintype "passive"))
      (node (ref "C214") (pin "2") (pinfunction "2_2") (pintype "passive"))
      (node (ref "C215") (pin "2") (pinfunction "2_2") (pintype "passive"))
      (node (ref "C216") (pin "2") (pinfunction "2_2") (pintype "passive"))
      (node (ref "C217") (pin "2") (pinfunction "2_2") (pintype "passive"))
      (node (ref "C218") (pin "2") (pinfunction "2_2") (pintype "passive"))
      (node (ref "C219") (pin "2") (pinfunction "2_2") (pintype "passive"))
      (node (ref "C22") (pin "2") (pinfunction "2_2") (pintype "passive"))
      (node (ref "C220") (pin "2") (pinfunction "2_2") (pintype "passive"))
      (node (ref "C221") (pin "2") (pinfunction "2_2") (pintype "passive"))
      (node (ref "C222") (pin "2") (pinfunction "2_2") (pintype "passive"))
      (node (ref "C223") (pin "2") (pinfunction "2_2") (pintype "passive"))
      (node (ref "C224") (pin "2") (pinfunction "2_2") (pintype "passive"))
      (node (ref "C225") (pin "2") (pinfunction "2_2") (pintype "passive"))
      (node (ref "C226") (pin "2") (pinfunction "2_2") (pintype "passive"))
      (node (ref "C227") (pin "2") (pinfunction "2_2") (pintype "passive"))
      (node (ref "C228") (pin "2") (pinfunction "2_2") (pintype "passive"))
      (node (ref "C229") (pin "2") (pinfunction "2_2") (pintype "passive"))
      (node (ref "C23") (pin "2") (pinfunction "2_2") (pintype "passive"))
      (node (ref "C230") (pin "2") (pinfunction "2_2") (pintype "passive"))
      (node (ref "C231") (pin "2") (pinfunction "2_2") (pintype "passive"))
      (node (ref "C232") (pin "2") (pinfunction "2_2") (pintype "passive"))
      (node (ref "C233") (pin "2") (pinfunction "2_2") (pintype "passive"))
      (node (ref "C234") (pin "2") (pinfunction "2_2") (pintype "passive"))
      (node (ref "C235") (pin "2") (pinfunction "2_2") (pintype "passive"))
      (node (ref "C236") (pin "2") (pinfunction "2_2") (pintype "passive"))
      (node (ref "C237") (pin "2") (pinfunction "2_2") (pintype "passive"))
      (node (ref "C238") (pin "2") (pinfunction "2_2") (pintype "passive"))
      (node (ref "C239") (pin "2") (pinfunction "2_2") (pintype "passive"))
      (node (ref "C24") (pin "2") (pinfunction "2_2") (pintype "passive"))
      (node (ref "C240") (pin "2") (pinfunction "2_2") (pintype "passive"))
      (node (ref "C241") (pin "2") (pinfunction "2_2") (pintype "passive"))
      (node (ref "C242") (pin "2") (pinfunction "2_2") (pintype "passive"))
      (node (ref "C243") (pin "2") (pinfunction "2_2") (pintype "passive"))
      (node (ref "C244") (pin "2") (pinfunction "2_2") (pintype "passive"))
      (node (ref "C245") (pin "2") (pinfunction "2_2") (pintype "passive"))
      (node (ref "C246") (pin "2") (pinfunction "2_2") (pintype "passive"))
      (node (ref "C247") (pin "2") (pinfunction "2_2") (pintype "passive"))
      (node (ref "C248") (pin "2") (pinfunction "2_2") (pintype "passive"))
      (node (ref "C249") (pin "2") (pinfunction "2_2") (pintype "passive"))
      (node (ref "C25") (pin "2") (pinfunction "2_2") (pintype "passive"))
      (node (ref "C250") (pin "2") (pinfunction "2_2") (pintype "passive"))
      (node (ref "C251") (pin "2") (pinfunction "2_2") (pintype "passive"))
      (node (ref "C252") (pin "2") (pinfunction "2_2") (pintype "passive"))
      (node (ref "C253") (pin "2") (pinfunction "2_2") (pintype "passive"))
      (node (ref "C254") (pin "2") (pinfunction "2_2") (pintype "passive"))
      (node (ref "C255") (pin "2") (pinfunction "2_2") (pintype "passive"))
      (node (ref "C256") (pin "2") (pinfunction "2_2") (pintype "passive"))
      (node (ref "C257") (pin "2") (pinfunction "2_2") (pintype "passive"))
      (node (ref "C258") (pin "2") (pinfunction "2_2") (pintype "passive"))
      (node (ref "C259") (pin "2") (pinfunction "2_2") (pintype "passive"))
      (node (ref "C26") (pin "2") (pinfunction "2_2") (pintype "passive"))
      (node (ref "C260") (pin "2") (pinfunction "2_2") (pintype "passive"))
      (node (ref "C261") (pin "2") (pinfunction "2_2") (pintype "passive"))
      (node (ref "C262") (pin "2") (pinfunction "2_2") (pintype "passive"))
      (node (ref "C263") (pin "2") (pinfunction "2_2") (pintype "passive"))
      (node (ref "C264") (pin "2") (pinfunction "2_2") (pintype "passive"))
      (node (ref "C265") (pin "2") (pinfunction "2_2") (pintype "passive"))
      (node (ref "C266") (pin "2") (pinfunction "2_2") (pintype "passive"))
      (node (ref "C267") (pin "2") (pinfunction "2_2") (pintype "passive"))
      (node (ref "C268") (pin "2") (pinfunction "2_2") (pintype "passive"))
      (node (ref "C269") (pin "2") (pinfunction "2_2") (pintype "passive"))
      (node (ref "C27") (pin "2") (pinfunction "2_2") (pintype "passive"))
      (node (ref "C270") (pin "2") (pinfunction "2_2") (pintype "passive"))
      (node (ref "C271") (pin "2") (pinfunction "2_2") (pintype "passive"))
      (node (ref "C272") (pin "2") (pinfunction "2_2") (pintype "passive"))
      (node (ref "C273") (pin "2") (pinfunction "2_2") (pintype "passive"))
      (node (ref "C274") (pin "2") (pinfunction "2_2") (pintype "passive"))
      (node (ref "C275") (pin "2") (pinfunction "2_2") (pintype "passive"))
      (node (ref "C276") (pin "2") (pinfunction "2_2") (pintype "passive"))
      (node (ref "C277") (pin "2") (pinfunction "2_2") (pintype "passive"))
      (node (ref "C278") (pin "2") (pinfunction "2_2") (pintype "passive"))
      (node (ref "C279") (pin "2") (pinfunction "2_2") (pintype "passive"))
      (node (ref "C28") (pin "2") (pinfunction "2_2") (pintype "passive"))
      (node (ref "C280") (pin "2") (pinfunction "2_2") (pintype "passive"))
      (node (ref "C281") (pin "2") (pinfunction "2_2") (pintype "passive"))
      (node (ref "C282") (pin "2") (pinfunction "2_2") (pintype "passive"))
      (node (ref "C283") (pin "2") (pinfunction "2_2") (pintype "passive"))
      (node (ref "C284") (pin "2") (pinfunction "2_2") (pintype "passive"))
      (node (ref "C285") (pin "2") (pinfunction "2_2") (pintype "passive"))
      (node (ref "C286") (pin "2") (pinfunction "2_2") (pintype "passive"))
      (node (ref "C287") (pin "2") (pinfunction "2_2") (pintype "passive"))
      (node (ref "C288") (pin "2") (pinfunction "2_2") (pintype "passive"))
      (node (ref "C289") (pin "2") (pinfunction "2_2") (pintype "passive"))
      (node (ref "C29") (pin "2") (pinfunction "2_2") (pintype "passive"))
      (node (ref "C290") (pin "2") (pinfunction "2_2") (pintype "passive"))
      (node (ref "C291") (pin "2") (pinfunction "2_2") (pintype "passive"))
      (node (ref "C292") (pin "2") (pinfunction "2_2") (pintype "passive"))
      (node (ref "C293") (pin "2") (pinfunction "2_2") (pintype "passive"))
      (node (ref "C294") (pin "2") (pinfunction "2_2") (pintype "passive"))
      (node (ref "C295") (pin "2") (pinfunction "2_2") (pintype "passive"))
      (node (ref "C296") (pin "2") (pinfunction "2_2") (pintype "passive"))
      (node (ref "C297") (pin "2") (pinfunction "2_2") (pintype "passive"))
      (node (ref "C298") (pin "2") (pinfunction "2_2") (pintype "passive"))
      (node (ref "C299") (pin "2") (pinfunction "2_2") (pintype "passive"))
      (node (ref "C3") (pin "2") (pinfunction "2_2") (pintype "passive"))
      (node (ref "C30") (pin "2") (pinfunction "2_2") (pintype "passive"))
      (node (ref "C300") (pin "2") (pinfunction "2_2") (pintype "passive"))
      (node (ref "C31") (pin "2") (pinfunction "2_2") (pintype "passive"))
      (node (ref "C32") (pin "2") (pinfunction "2_2") (pintype "passive"))
      (node (ref "C33") (pin "2") (pinfunction "2_2") (pintype "passive"))
      (node (ref "C34") (pin "2") (pinfunction "2_2") (pintype "passive"))
      (node (ref "C35") (pin "2") (pinfunction "2_2") (pintype "passive"))
      (node (ref "C36") (pin "2") (pinfunction "2_2") (pintype "passive"))
      (node (ref "C37") (pin "2") (pinfunction "2_2") (pintype "passive"))
      (node (ref "C38") (pin "2") (pinfunction "2_2") (pintype "passive"))
      (node (ref "C39") (pin "2") (pinfunction "2_2") (pintype "passive"))
      (node (ref "C4") (pin "2") (pinfunction "2_2") (pintype "passive"))
      (node (ref "C40") (pin "2") (pinfunction "2_2") (pintype "passive"))
      (node (ref "C41") (pin "2") (pinfunction "2_2") (pintype "passive"))
      (node (ref "C42") (pin "2") (pinfunction "2_2") (pintype "passive"))
      (node (ref "C43") (pin "2") (pinfunction "2_2") (pintype "passive"))
      (node (ref "C44") (pin "2") (pinfunction "2_2") (pintype "passive"))
      (node (ref "C45") (pin "2") (pinfunction "2_2") (pintype "passive"))
      (node (ref "C46") (pin "2") (pinfunction "2_2") (pintype "passive"))
      (node (ref "C47") (pin "2") (pinfunction "2_2") (pintype "passive"))
      (node (ref "C48") (pin "2") (pinfunction "2_2") (pintype "passive"))
      (node (ref "C49") (pin "2") (pinfunction "2_2") (pintype "passive"))
      (node (ref "C5") (pin "2") (pinfunction "2_2") (pintype "passive"))
      (node (ref "C50") (pin "2") (pinfunction "2_2") (pintype "passive"))
      (node (ref "C51") (pin "2") (pinfunction "2_2") (pintype "passive"))
      (node (ref "C52") (pin "2") (pinfunction "2_2") (pintype "passive"))
      (node (ref "C53") (pin "2") (pinfunction "2_2") (pintype "passive"))
      (node (ref "C54") (pin "2") (pinfunction "2_2") (pintype "passive"))
      (node (ref "C55") (pin "2") (pinfunction "2_2") (pintype "passive"))
      (node (ref "C56") (pin "2") (pinfunction "2_2") (pintype "passive"))
      (node (ref "C57") (pin "2") (pinfunction "2_2") (pintype "passive"))
      (node (ref "C58") (pin "2") (pinfunction "2_2") (pintype "passive"))
      (node (ref "C59") (pin "2") (pinfunction "2_2") (pintype "passive"))
      (node (ref "C6") (pin "2") (pinfunction "2_2") (pintype "passive"))
      (node (ref "C60") (pin "2") (pinfunction "2_2") (pintype "passive"))
      (node (ref "C61") (pin "2") (pinfunction "2_2") (pintype "passive"))
      (node (ref "C62") (pin "2") (pinfunction "2_2") (pintype "passive"))
      (node (ref "C63") (pin "2") (pinfunction "2_2") (pintype "passive"))
      (node (ref "C64") (pin "2") (pinfunction "2_2") (pintype "passive"))
      (node (ref "C65") (pin "2") (pinfunction "2_2") (pintype "passive"))
      (node (ref "C66") (pin "2") (pinfunction "2_2") (pintype "passive"))
      (node (ref "C67") (pin "2") (pinfunction "2_2") (pintype "passive"))
      (node (ref "C68") (pin "2") (pinfunction "2_2") (pintype "passive"))
      (node (ref "C69") (pin "2") (pinfunction "2_2") (pintype "passive"))
      (node (ref "C7") (pin "2") (pinfunction "2_2") (pintype "passive"))
      (node (ref "C70") (pin "2") (pinfunction "2_2") (pintype "passive"))
      (node (ref "C71") (pin "2") (pinfunction "2_2") (pintype "passive"))
      (node (ref "C72") (pin "2") (pinfunction "2_2") (pintype "passive"))
      (node (ref "C73") (pin "2") (pinfunction "2_2") (pintype "passive"))
      (node (ref "C74") (pin "2") (pinfunction "2_2") (pintype "passive"))
      (node (ref "C75") (pin "2") (pinfunction "2_2") (pintype "passive"))
      (node (ref "C76") (pin "2") (pinfunction "2_2") (pintype "passive"))
      (node (ref "C77") (pin "2") (pinfunction "2_2") (pintype "passive"))
      (node (ref "C78") (pin "2") (pinfunction "2_2") (pintype "passive"))
      (node (ref "C79") (pin "2") (pinfunction "2_2") (pintype "passive"))
      (node (ref "C8") (pin "2") (pinfunction "2_2") (pintype "passive"))
      (node (ref "C80") (pin "2") (pinfunction "2_2") (pintype "passive"))
      (node (ref "C81") (pin "2") (pinfunction "2_2") (pintype "passive"))
      (node (ref "C82") (pin "2") (pinfunction "2_2") (pintype "passive"))
      (node (ref "C83") (pin "2") (pinfunction "2_2") (pintype "passive"))
      (node (ref "C84") (pin "2") (pinfunction "2_2") (pintype "passive"))
      (node (ref "C85") (pin "2") (pinfunction "2_2") (pintype "passive"))
      (node (ref "C86") (pin "2") (pinfunction "2_2") (pintype "passive"))
      (node (ref "C87") (pin "2") (pinfunction "2_2") (pintype "passive"))
      (node (ref "C88") (pin "2") (pinfunction "2_2") (pintype "passive"))
      (node (ref "C89") (pin "2") (pinfunction "2_2") (pintype "passive"))
      (node (ref "C9") (pin "2") (pinfunction "2_2") (pintype "passive"))
      (node (ref "C90") (pin "2") (pinfunction "2_2") (pintype "passive"))
      (node (ref "C91") (pin "2") (pinfunction "2_2") (pintype "passive"))
      (node (ref "C92") (pin "2") (pinfunction "2_2") (pintype "passive"))
      (node (ref "C93") (pin "2") (pinfunction "2_2") (pintype "passive"))
      (node (ref "C94") (pin "2") (pinfunction "2_2") (pintype "passive"))
      (node (ref "C95") (pin "2") (pinfunction "2_2") (pintype "passive"))
      (node (ref "C96") (pin "2") (pinfunction "2_2") (pintype "passive"))
      (node (ref "C97") (pin "2") (pinfunction "2_2") (pintype "passive"))
      (node (ref "C98") (pin "2") (pinfunction "2_2") (pintype "passive"))
      (node (ref "C99") (pin "2") (pinfunction "2_2") (pintype "passive"))
      (node (ref "J1") (pin "MP1") (pinfunction "MP1_MP1") (pintype "passive"))
      (node (ref "J1") (pin "MP2") (pinfunction "MP2_MP2") (pintype "passive"))
      (node (ref "J2") (pin "MP1") (pinfunction "MP1_MP1") (pintype "passive"))
      (node (ref "J2") (pin "MP2") (pinfunction "MP2_MP2") (pintype "passive"))
    )
    (net (code "2") (name "Net-(C1-Pad1)") (class "Default")
      (node (ref "C1") (pin "1") (pinfunction "1_1") (pintype "passive"))
      (node (ref "C51") (pin "1") (pinfunction "1_1") (pintype "passive"))
      (node (ref "R1") (pin "2") (pinfunction "2_2") (pintype "passive"))
      (node (ref "R51") (pin "1") (pinfunction "1_1") (pintype "passive"))
    )
    (net (code "3") (name "Net-(C2-Pad1)") (class "Default")
      (node (ref "C2") (pin "1") (pinfunction "1_1") (pintype "passive"))
      (node (ref "C52") (pin "1") (pinfunction "1_1") (pintype "passive"))
      (node (ref "R2") (pin "2") (pinfunction "2_2") (pintype "passive"))
      (node (ref "R52") (pin "1") (pinfunction "1_1") (pintype "passive"))
    )
    (net (code "4") (name "Net-(C3-Pad1)") (class "Default")
      (node (ref "C3") (pin "1") (pinfunction "1_1") (pintype "passive"))
      (node (ref "C53") (pin "1") (pinfunction "1_1") (pintype "passive"))
      (node (ref "R3") (pin "2") (pinfunction "2_2") (pintype "passive"))
      (node (ref "R53") (pin "1") (pinfunction "1_1") (pintype "passive"))
    )
    (net (code "5") (name "Net-(C4-Pad1)") (class "Default")
      (node (ref "C4") (pin "1") (pinfunction "1_1") (pintype "passive"))
      (node (ref "C54") (pin "1") (pinfunction "1_1") (pintype "passive"))
      (node (ref "R4") (pin "2") (pinfunction "2_2") (pintype "passive"))
      (node (ref "R54") (pin "1") (pinfunction "1_1") (pintype "passive"))
    )
    (net (code "6") (name "Net-(C5-Pad1)") (class "Default")
      (node (ref "C5") (pin "1") (pinfunction "1_1") (pintype "passive"))
      (node (ref "C55") (pin "1") (pinfunction "1_1") (pintype "passive"))
      (node (ref "R5") (pin "2") (pinfunction "2_2") (pintype "passive"))
      (node (ref "R55") (pin "1") (pinfunction "1_1") (pintype "passive"))
    )
    (net (code "7") (name "Net-(C10-Pad1)") (class "Default")
      (node (ref "C10") (pin "1") (pinfunction "1_1") (pintype "passive"))
      (node (ref "C60") (pin "1") (pinfunction "1_1") (pintype "passive"))
      (node (ref "R10") (pin "2") (pinfunction "2_2") (pintype "passive"))
      (node (ref "R60") (pin "1") (pinfunction "1_1") (pintype "passive"))
    )
    (net (code "8") (name "Net-(C11-Pad1)") (class "Default")
      (node (ref "C11") (pin "1") (pinfunction "1_1") (pintype "passive"))
      (node (ref "C61") (pin "1") (pinfunction "1_1") (pintype "passive"))
      (node (ref "R11") (pin "2") (pinfunction "2_2") (pintype "passive"))
      (node (ref "R61") (pin "1") (pinfunction "1_1") (pintype "passive"))
    )
    (net (code "9") (name "Net-(C12-Pad1)") (class "Default")
      (node (ref "C12") (pin "1") (pinfunction "1_1") (pintype "passive"))
      (node (ref "C62") (pin "1") (pinfunction "1_1") (pintype "passive"))
      (node (ref "R12") (pin "2") (pinfunction "2_2") (pintype "passive"))
      (node (ref "R62") (pin "1") (pinfunction "1_1") (pintype "passive"))
    )
    (net (code "10") (name "Net-(C13-Pad1)") (class "Default")
      (node (ref "C13") (pin "1") (pinfunction "1_1") (pintype "passive"))
      (node (ref "C63") (pin "1") (pinfunction "1_1") (pintype "passive"))
      (node (ref "R13") (pin "2") (pinfunction "2_2") (pintype "passive"))
      (node (ref "R63") (pin "1") (pinfunction "1_1") (pintype "passive"))
    )
    (net (code "11") (name "Net-(C14-Pad1)") (class "Default")
      (node (ref "C14") (pin "1") (pinfunction "1_1") (pintype "passive"))
      (node (ref "C64") (pin "1") (pinfunction "1_1") (pintype "passive"))
      (node (ref "R14") (pin "2") (pinfunction "2_2") (pintype "passive"))
      (node (ref "R64") (pin "1") (pinfunction "1_1") (pintype "passive"))
    )
    (net (code "12") (name "Net-(C15-Pad1)") (class "Default")
      (node (ref "C15") (pin "1") (pinfunction "1_1") (pintype "passive"))
      (node (ref "C65") (pin "1") (pinfunction "1_1") (pintype "passive"))
      (node (ref "R15") (pin "2") (pinfunction "2_2") (pintype "passive"))
      (node (ref "R65") (pin "1") (pinfunction "1_1") (pintype "passive"))
    )
    (net (code "13") (name "Net-(C16-Pad1)") (class "Default")
      (node (ref "C16") (pin "1") (pinfunction "1_1") (pintype "passive"))
      (node (ref "C66") (pin "1") (pinfunction "1_1") (pintype "passive"))
      (node (ref "R16") (pin "2") (pinfunction "2_2") (pintype "passive"))
      (node (ref "R66") (pin "1") (pinfunction "1_1") (pintype "passive"))
    )
    (net (code "14") (name "Net-(C17-Pad1)") (class "Default")
      (node (ref "C17") (pin "1") (pinfunction "1_1") (pintype "passive"))
      (node (ref "C67") (pin "1") (pinfunction "1_1") (pintype "passive"))
      (node (ref "R17") (pin "2") (pinfunction "2_2") (pintype "passive"))
      (node (ref "R67") (pin "1") (pinfunction "1_1") (pintype "passive"))
    )
    (net (code "15") (name "Net-(C18-Pad1)") (class "Default")
      (node (ref "C18") (pin "1") (pinfunction "1_1") (pintype "passive"))
      (node (ref "C68") (pin "1") (pinfunction "1_1") (pintype "passive"))
      (node (ref "R18") (pin "2") (pinfunction "2_2") (pintype "passive"))
      (node (ref "R68") (pin "1") (pinfunction "1_1") (pintype "passive"))
    )
    (net (code "16") (name "Net-(C19-Pad1)") (class "Default")
      (node (ref "C19") (pin "1") (pinfunction "1_1") (pintype "passive"))
      (node (ref "C69") (pin "1") (pinfunction "1_1") (pintype "passive"))
      (node (ref "R19") (pin "2") (pinfunction "2_2") (pintype "passive"))
      (node (ref "R69") (pin "1") (pinfunction "1_1") (pintype "passive"))
    )
    (net (code "17") (name "Net-(C20-Pad1)") (class "Default")
      (node (ref "C20") (pin "1") (pinfunction "1_1") (pintype "passive"))
      (node (ref "C70") (pin "1") (pinfunction "1_1") (pintype "passive"))
      (node (ref "R20") (pin "2") (pinfunction "2_2") (pintype "passive"))
      (node (ref "R70") (pin "1") (pinfunction "1_1") (pintype "passive"))
    )
    (net (code "18") (name "Net-(C21-Pad1)") (class "Default")
      (node (ref "C21") (pin "1") (pinfunction "1_1") (pintype "passive"))
      (node (ref "C71") (pin "1") (pinfunction "1_1") (pintype "passive"))
      (node (ref "R21") (pin "2") (pinfunction "2_2") (pintype "passive"))
      (node (ref "R71") (pin "1") (pinfunction "1_1") (pintype "passive"))
    )
    (net (code "19") (name "Net-(C22-Pad1)") (class "Default")
      (node (ref "C22") (pin "1") (pinfunction "1_1") (pintype "passive"))
      (node (ref "C72") (pin "1") (pinfunction "1_1") (pintype "passive"))
      (node (ref "R22") (pin "2") (pinfunction "2_2") (pintype "passive"))
      (node (ref "R72") (pin "1") (pinfunction "1_1") (pintype "passive"))
    )
    (net (code "20") (name "Net-(C23-Pad1)") (class "Default")
      (node (ref "C23") (pin "1") (pinfunction "1_1") (pintype "passive"))
      (node (ref "C73") (pin "1") (pinfunction "1_1") (pintype "passive"))
      (node (ref "R23") (pin "2") (pinfunction "2_2") (pintype "passive"))
      (node (ref "R73") (pin "1") (pinfunction "1_1") (pintype "passive"))
    )
    (net (code "21") (name "Net-(C24-Pad1)") (class "Default")
      (node (ref "C24") (pin "1") (pinfunction "1_1") (pintype "passive"))
      (node (ref "C74") (pin "1") (pinfunction "1_1") (pintype "passive"))
      (node (ref "R24") (pin "2") (pinfunction "2_2") (pintype "passive"))
      (node (ref "R74") (pin "1") (pinfunction "1_1") (pintype "passive"))
    )
    (net (code "22") (name "Net-(C25-Pad1)") (class "Default")
      (node (ref "C25") (pin "1") (pinfunction "1_1") (pintype "passive"))
      (node (ref "C75") (pin "1") (pinfunction "1_1") (pintype "passive"))
      (node (ref "R25") (pin "2") (pinfunction "2_2") (pintype "passive"))
      (node (ref "R75") (pin "1") (pinfunction "1_1") (pintype "passive"))
    )
    (net (code "23") (name "Net-(C26-Pad1)") (class "Default")
      (node (ref "C26") (pin "1") (pinfunction "1_1") (pintype "passive"))
      (node (ref "C76") (pin "1") (pinfunction "1_1") (pintype "passive"))
      (node (ref "R26") (pin "2") (pinfunction "2_2") (pintype "passive"))
      (node (ref "R76") (pin "1") (pinfunction "1_1") (pintype "passive"))
    )
    (net (code "24") (name "Net-(C27-Pad1)") (class "Default")
      (node (ref "C27") (pin "1") (pinfunction "1_1") (pintype "passive"))
      (node (ref "C77") (pin "1") (pinfunction "1_1") (pintype "passive"))
      (node (ref "R27") (pin "2") (pinfunction "2_2") (pintype "passive"))
      (node (ref "R77") (pin "1") (pinfunction "1_1") (pintype "passive"))
    )
    (net (code "25") (name "Net-(C28-Pad1)") (class "Default")
      (node (ref "C28") (pin "1") (pinfunction "1_1") (pintype "passive"))
      (node (ref "C78") (pin "1") (pinfunction "1_1") (pintype "passive"))
      (node (ref "R28") (pin "2") (pinfunction "2_2") (pintype "passive"))
      (node (ref "R78") (pin "1") (pinfunction "1_1") (pintype "passive"))
    )
    (net (code "26") (name "Net-(C29-Pad1)") (class "Default")
      (node (ref "C29") (pin "1") (pinfunction "1_1") (pintype "passive"))
      (node (ref "C79") (pin "1") (pinfunction "1_1") (pintype "passive"))
      (node (ref "R29") (pin "2") (pinfunction "2_2") (pintype "passive"))
      (node (ref "R79") (pin "1") (pinfunction "1_1") (pintype "passive"))
    )
    (net (code "27") (name "Net-(C30-Pad1)") (class "Default")
      (node (ref "C30") (pin "1") (pinfunction "1_1") (pintype "passive"))
      (node (ref "C80") (pin "1") (pinfunction "1_1") (pintype "passive"))
      (node (ref "R30") (pin "2") (pinfunction "2_2") (pintype "passive"))
      (node (ref "R80") (pin "1") (pinfunction "1_1") (pintype "passive"))
    )
    (net (code "28") (name "Net-(C31-Pad1)") (class "Default")
      (node (ref "C31") (pin "1") (pinfunction "1_1") (pintype "passive"))
      (node (ref "C81") (pin "1") (pinfunction "1_1") (pintype "passive"))
      (node (ref "R31") (pin "2") (pinfunction "2_2") (pintype "passive"))
      (node (ref "R81") (pin "1") (pinfunction "1_1") (pintype "passive"))
    )
    (net (code "29") (name "Net-(C32-Pad1)") (class "Default")
      (node (ref "C32") (pin "1") (pinfunction "1_1") (pintype "passive"))
      (node (ref "C82") (pin "1") (pinfunction "1_1") (pintype "passive"))
      (node (ref "R32") (pin "2") (pinfunction "2_2") (pintype "passive"))
      (node (ref "R82") (pin "1") (pinfunction "1_1") (pintype "passive"))
    )
    (net (code "30") (name "Net-(C33-Pad1)") (class "Default")
      (node (ref "C33") (pin "1") (pinfunction "1_1") (pintype "passive"))
      (node (ref "C83") (pin "1") (pinfunction "1_1") (pintype "passive"))
      (node (ref "R33") (pin "2") (pinfunction "2_2") (pintype "passive"))
      (node (ref "R83") (pin "1") (pinfunction "1_1") (pintype "passive"))
    )
    (net (code "31") (name "Net-(C34-Pad1)") (class "Default")
      (node (ref "C34") (pin "1") (pinfunction "1_1") (pintype "passive"))
      (node (ref "C84") (pin "1") (pinfunction "1_1") (pintype "passive"))
      (node (ref "R34") (pin "2") (pinfunction "2_2") (pintype "passive"))
      (node (ref "R84") (pin "1") (pinfunction "1_1") (pintype "passive"))
    )
    (net (code "32") (name "Net-(C35-Pad1)") (class "Default")
      (node (ref "C35") (pin "1") (pinfunction "1_1") (pintype "passive"))
      (node (ref "C85") (pin "1") (pinfunction "1_1") (pintype "passive"))
      (node (ref "R35") (pin "2") (pinfunction "2_2") (pintype "passive"))
      (node (ref "R85") (pin "1") (pinfunction "1_1") (pintype "passive"))
    )
    (net (code "33") (name "Net-(C36-Pad1)") (class "Default")
      (node (ref "C36") (pin "1") (pinfunction "1_1") (pintype "passive"))
      (node (ref "C86") (pin "1") (pinfunction "1_1") (pintype "passive"))
      (node (ref "R36") (pin "2") (pinfunction "2_2") (pintype "passive"))
      (node (ref "R86") (pin "1") (pinfunction "1_1") (pintype "passive"))
    )
    (net (code "34") (name "Net-(C37-Pad1)") (class "Default")
      (node (ref "C37") (pin "1") (pinfunction "1_1") (pintype "passive"))
      (node (ref "C87") (pin "1") (pinfunction "1_1") (pintype "passive"))
      (node (ref "R37") (pin "2") (pinfunction "2_2") (pintype "passive"))
      (node (ref "R87") (pin "1") (pinfunction "1_1") (pintype "passive"))
    )
    (net (code "35") (name "Net-(C38-Pad1)") (class "Default")
      (node (ref "C38") (pin "1") (pinfunction "1_1") (pintype "passive"))
      (node (ref "C88") (pin "1") (pinfunction "1_1") (pintype "passive"))
      (node (ref "R38") (pin "2") (pinfunction "2_2") (pintype "passive"))
      (node (ref "R88") (pin "1") (pinfunction "1_1") (pintype "passive"))
    )
    (net (code "36") (name "Net-(C39-Pad1)") (class "Default")
      (node (ref "C39") (pin "1") (pinfunction "1_1") (pintype "passive"))
      (node (ref "C89") (pin "1") (pinfunction "1_1") (pintype "passive"))
      (node (ref "R39") (pin "2") (pinfunction "2_2") (pintype "passive"))
      (node (ref "R89") (pin "1") (pinfunction "1_1") (pintype "passive"))
    )
    (net (code "37") (name "Net-(C40-Pad1)") (class "Default")
      (node (ref "C40") (pin "1") (pinfunction "1_1") (pintype "passive"))
      (node (ref "C90") (pin "1") (pinfunction "1_1") (pintype "passive"))
      (node (ref "R40") (pin "2") (pinfunction "2_2") (pintype "passive"))
      (node (ref "R90") (pin "1") (pinfunction "1_1") (pintype "passive"))
    )
    (net (code "38") (name "Net-(C41-Pad1)") (class "Default")
      (node (ref "C41") (pin "1") (pinfunction "1_1") (pintype "passive"))
      (node (ref "C91") (pin "1") (pinfunction "1_1") (pintype "passive"))
      (node (ref "R41") (pin "2") (pinfunction "2_2") (pintype "passive"))
      (node (ref "R91") (pin "1") (pinfunction "1_1") (pintype "passive"))
    )
    (net (code "39") (name "Net-(C42-Pad1)") (class "Default")
      (node (ref "C42") (pin "1") (pinfunction "1_1") (pintype "passive"))
      (node (ref "C92") (pin "1") (pinfunction "1_1") (pintype "passive"))
      (node (ref "R42") (pin "2") (pinfunction "2_2") (pintype "passive"))
      (node (ref "R92") (pin "1") (pinfunction "1_1") (pintype "passive"))
    )
    (net (code "40") (name "Net-(C43-Pad1)") (class "Default")
      (node (ref "C43") (pin "1") (pinfunction "1_1") (pintype "passive"))
      (node (ref "C93") (pin "1") (pinfunction "1_1") (pintype "passive"))
      (node (ref "R43") (pin "2") (pinfunction "2_2") (pintype "passive"))
      (node (ref "R93") (pin "1") (pinfunction "1_1") (pintype "passive"))
    )
    (net (code "41") (name "Net-(C44-Pad1)") (class "Default")
      (node (ref "C44") (pin "1") (pinfunction "1_1") (pintype "passive"))
      (node (ref "C94") (pin "1") (pinfunction "1_1") (pintype "passive"))
      (node (ref "R44") (pin "2") (pinfunction "2_2") (pintype "passive"))
      (node (ref "R94") (pin "1") (pinfunction "1_1") (pintype "passive"))
    )
    (net (code "42") (name "Net-(C45-Pad1)") (class "Default")
      (node (ref "C45") (pin "1") (pinfunction "1_1") (pintype "passive"))
      (node (ref "C95") (pin "1") (pinfunction "1_1") (pintype "passive"))
      (node (ref "R45") (pin "2") (pinfunction "2_2") (pintype "passive"))
      (node (ref "R95") (pin "1") (pinfunction "1_1") (pintype "passive"))
    )
    (net (code "43") (name "Net-(C46-Pad1)") (class "Default")
      (node (ref "C46") (pin "1") (pinfunction "1_1") (pintype "passive"))
      (node (ref "C96") (pin "1") (pinfunction "1_1") (pintype "passive"))
      (node (ref "R46") (pin "2") (pinfunction "2_2") (pintype "passive"))
      (node (ref "R96") (pin "1") (pinfunction "1_1") (pintype "passive"))
    )
    (net (code "44") (name "Net-(C47-Pad1)") (class "Default")
      (node (ref "C47") (pin "1") (pinfunction "1_1") (pintype "passive"))
      (node (ref "C97") (pin "1") (pinfunction "1_1") (pintype "passive"))
      (node (ref "R47") (pin "2") (pinfunction "2_2") (pintype "passive"))
      (node (ref "R97") (pin "1") (pinfunction "1_1") (pintype "passive"))
    )
    (net (code "45") (name "Net-(C48-Pad1)") (class "Default")
      (node (ref "C48") (pin "1") (pinfunction "1_1") (pintype "passive"))
      (node (ref "C98") (pin "1") (pinfunction "1_1") (pintype "passive"))
      (node (ref "R48") (pin "2") (pinfunction "2_2") (pintype "passive"))
      (node (ref "R98") (pin "1") (pinfunction "1_1") (pintype "passive"))
    )
    (net (code "46") (name "Net-(C49-Pad1)") (class "Default")
      (node (ref "C49") (pin "1") (pinfunction "1_1") (pintype "passive"))
      (node (ref "C99") (pin "1") (pinfunction "1_1") (pintype "passive"))
      (node (ref "R49") (pin "2") (pinfunction "2_2") (pintype "passive"))
      (node (ref "R99") (pin "1") (pinfunction "1_1") (pintype "passive"))
    )
    (net (code "47") (name "Net-(C56-Pad1)") (class "Default")
      (node (ref "C56") (pin "1") (pinfunction "1_1") (pintype "passive"))
      (node (ref "C6") (pin "1") (pinfunction "1_1") (pintype "passive"))
      (node (ref "R56") (pin "1") (pinfunction "1_1") (pintype "passive"))
      (node (ref "R6") (pin "2") (pinfunction "2_2") (pintype "passive"))
    )
    (net (code "48") (name "Net-(C57-Pad1)") (class "Default")
      (node (ref "C57") (pin "1") (pinfunction "1_1") (pintype "passive"))
      (node (ref "C7") (pin "1") (pinfunction "1_1") (pintype "passive"))
      (node (ref "R57") (pin "1") (pinfunction "1_1") (pintype "passive"))
      (node (ref "R7") (pin "2") (pinfunction "2_2") (pintype "passive"))
    )
    (net (code "49") (name "Net-(C58-Pad1)") (class "Default")
      (node (ref "C58") (pin "1") (pinfunction "1_1") (pintype "passive"))
      (node (ref "C8") (pin "1") (pinfunction "1_1") (pintype "passive"))
      (node (ref "R58") (pin "1") (pinfunction "1_1") (pintype "passive"))
      (node (ref "R8") (pin "2") (pinfunction "2_2") (pintype "passive"))
    )
    (net (code "50") (name "Net-(C59-Pad1)") (class "Default")
      (node (ref "C59") (pin "1") (pinfunction "1_1") (pintype "passive"))
      (node (ref "C9") (pin "1") (pinfunction "1_1") (pintype "passive"))
      (node (ref "R59") (pin "1") (pinfunction "1_1") (pintype "passive"))
      (node (ref "R9") (pin "2") (pinfunction "2_2") (pintype "passive"))
    )
    (net (code "51") (name "Net-(C100-Pad1)") (class "Default")
      (node (ref "C100") (pin "1") (pinfunction "1_1") (pintype "passive"))
      (node (ref "C50") (pin "1") (pinfunction "1_1") (pintype "passive"))
      (node (ref "R100") (pin "1") (pinfunction "1_1") (pintype "passive"))
      (node (ref "R50") (pin "2") (pinfunction "2_2") (pintype "passive"))
    )
    (net (code "52") (name "Net-(C101-Pad1)") (class "Default")
      (node (ref "C101") (pin "1") (pinfunction "1_1") (pintype "passive"))
      (node (ref "C151") (pin "1") (pinfunction "1_1") (pintype "passive"))
      (node (ref "R101") (pin "1") (pinfunction "1_1") (pintype "passive"))
      (node (ref "R51") (pin "2") (pinfunction "2_2") (pintype "passive"))
    )
    (net (code "53") (name "Net-(C102-Pad1)") (class "Default")
      (node (ref "C102") (pin "1") (pinfunction "1_1") (pintype "passive"))
      (node (ref "C152") (pin "1") (pinfunction "1_1") (pintype "passive"))
      (node (ref "R102") (pin "1") (pinfunction "1_1") (pintype "passive"))
      (node (ref "R52") (pin "2") (pinfunction "2_2") (pintype "passive"))
    )
    (net (code "54") (name "Net-(C103-Pad1)") (class "Default")
      (node (ref "C103") (pin "1") (pinfunction "1_1") (pintype "passive"))
      (node (ref "C153") (pin "1") (pinfunction "1_1") (pintype "passive"))
      (node (ref "R103") (pin "1") (pinfunction "1_1") (pintype "passive"))
      (node (ref "R53") (pin "2") (pinfunction "2_2") (pintype "passive"))
    )
    (net (code "55") (name "Net-(C104-Pad1)") (class "Default")
      (node (ref "C104") (pin "1") (pinfunction "1_1") (pintype "passive"))
      (node (ref "C154") (pin "1") (pinfunction "1_1") (pintype "passive"))
      (node (ref "R104") (pin "1") (pinfunction "1_1") (pintype "passive"))
      (node (ref "R54") (pin "2") (pinfunction "2_2") (pintype "passive"))
    )
    (net (code "56") (name "Net-(C105-Pad1)") (class "Default")
      (node (ref "C105") (pin "1") (pinfunction "1_1") (pintype "passive"))
      (node (ref "C155") (pin "1") (pinfunction "1_1") (pintype "passive"))
      (node (ref "R105") (pin "1") (pinfunction "1_1") (pintype "passive"))
      (node (ref "R55") (pin "2") (pinfunction "2_2") (pintype "passive"))
    )
    (net (code "57") (name "Net-(C106-Pad1)") (class "Default")
      (node (ref "C106") (pin "1") (pinfunction "1_1") (pintype "passive"))
      (node (ref "C156") (pin "1") (pinfunction "1_1") (pintype "passive"))
      (node (ref "R106") (pin "1") (pinfunction "1_1") (pintype "passive"))
      (node (ref "R56") (pin "2") (pinfunction "2_2") (pintype "passive"))
    )
    (net (code "58") (name "Net-(C107-Pad1)") (class "Default")
      (node (ref "C107") (pin "1") (pinfunction "1_1") (pintype "passive"))
      (node (ref "C157") (pin "1") (pinfunction "1_1") (pintype "passive"))
      (node (ref "R107") (pin "1") (pinfunction "1_1") (pintype "passive"))
      (node (ref "R57") (pin "2") (pinfunction "2_2") (pintype "passive"))
    )
    (net (code "59") (name "Net-(C108-Pad1)") (class "Default")
      (node (ref "C108") (pin "1") (pinfunction "1_1") (pintype "passive"))
      (node (ref "C158") (pin "1") (pinfunction "1_1") (pintype "passive"))
      (node (ref "R108") (pin "1") (pinfunction "1_1") (pintype "passive"))
      (node (ref "R58") (pin "2") (pinfunction "2_2") (pintype "passive"))
    )
    (net (code "60") (name "Net-(C109-Pad1)") (class "Default")
      (node (ref "C109") (pin "1") (pinfunction "1_1") (pintype "passive"))
      (node (ref "C159") (pin "1") (pinfunction "1_1") (pintype "passive"))
      (node (ref "R109") (pin "1") (pinfunction "1_1") (pintype "passive"))
      (node (ref "R59") (pin "2") (pinfunction "2_2") (pintype "passive"))
    )
    (net (code "61") (name "Net-(C110-Pad1)") (class "Default")
      (node (ref "C110") (pin "1") (pinfunction "1_1") (pintype "passive"))
      (node (ref "C160") (pin "1") (pinfunction "1_1") (pintype "passive"))
      (node (ref "R110") (pin "1") (pinfunction "1_1") (pintype "passive"))
      (node (ref "R60") (pin "2") (pinfunction "2_2") (pintype "passive"))
    )
    (net (code "62") (name "Net-(C111-Pad1)") (class "Default")
      (node (ref "C111") (pin "1") (pinfunction "1_1") (pintype "passive"))
      (node (ref "C161") (pin "1") (pinfunction "1_1") (pintype "passive"))
      (node (ref "R111") (pin "1") (pinfunction "1_1") (pintype "passive"))
      (node (ref "R61") (pin "2") (pinfunction "2_2") (pintype "passive"))
    )
    (net (code "63") (name "Net-(C112-Pad1)") (class "Default")
      (node (ref "C112") (pin "1") (pinfunction "1_1") (pintype "passive"))
      (node (ref "C162") (pin "1") (pinfunction "1_1") (pintype "passive"))
      (node (ref "R112") (pin "1") (pinfunction "1_1") (pintype "passive"))
      (node (ref "R62") (pin "2") (pinfunction "2_2") (pintype "passive"))
    )
    (net (code "64") (name "Net-(C113-Pad1)") (class "Default")
      (node (ref "C113") (pin "1") (pinfunction "1_1") (pintype "passive"))
      (node (ref "C163") (pin "1") (pinfunction "1_1") (pintype "passive"))
      (node (ref "R113") (pin "1") (pinfunction "1_1") (pintype "passive"))
      (node (ref "R63") (pin "2") (pinfunction "2_2") (pintype "passive"))
    )
    (net (code "65") (name "Net-(C114-Pad1)") (class "Default")
      (node (ref "C114") (pin "1") (pinfunction "1_1") (pintype "passive"))
      (node (ref "C164") (pin "1") (pinfunction "1_1") (pintype "passive"))
      (node (ref "R114") (pin "1") (pinfunction "1_1") (pintype "passive"))
      (node (ref "R64") (pin "2") (pinfunction "2_2") (pintype "passive"))
    )
    (net (code "66") (name "Net-(C115-Pad1)") (class "Default")
      (node (ref "C115") (pin "1") (pinfunction "1_1") (pintype "passive"))
      (node (ref "C165") (pin "1") (pinfunction "1_1") (pintype "passive"))
      (node (ref "R115") (pin "1") (pinfunction "1_1") (pintype "passive"))
      (node (ref "R65") (pin "2") (pinfunction "2_2") (pintype "passive"))
    )
    (net (code "67") (name "Net-(C116-Pad1)") (class "Default")
      (node (ref "C116") (pin "1") (pinfunction "1_1") (pintype "passive"))
      (node (ref "C166") (pin "1") (pinfunction "1_1") (pintype "passive"))
      (node (ref "R116") (pin "1") (pinfunction "1_1") (pintype "passive"))
      (node (ref "R66") (pin "2") (pinfunction "2_2") (pintype "passive"))
    )
    (net (code "68") (name "Net-(C117-Pad1)") (class "Default")
      (node (ref "C117") (pin "1") (pinfunction "1_1") (pintype "passive"))
      (node (ref "C167") (pin "1") (pinfunction "1_1") (pintype "passive"))
      (node (ref "R117") (pin "1") (pinfunction "1_1") (pintype "passive"))
      (node (ref "R67") (pin "2") (pinfunction "2_2") (pintype "passive"))
    )
    (net (code "69") (name "Net-(C118-Pad1)") (class "Default")
      (node (ref "C118") (pin "1") (pinfunction "1_1") (pintype "passive"))
      (node (ref "C168") (pin "1") (pinfunction "1_1") (pintype "passive"))
      (node (ref "R118") (pin "1") (pinfunction "1_1") (pintype "passive"))
      (node (ref "R68") (pin "2") (pinfunction "2_2") (pintype "passive"))
    )
    (net (code "70") (name "Net-(C119-Pad1)") (class "Default")
      (node (ref "C119") (pin "1") (pinfunction "1_1") (pintype "passive"))
      (node (ref "C169") (pin "1") (pinfunction "1_1") (pintype "passive"))
      (node (ref "R119") (pin "1") (pinfunction "1_1") (pintype "passive"))
      (node (ref "R69") (pin "2") (pinfunction "2_2") (pintype "passive"))
    )
    (net (code "71") (name "Net-(C120-Pad1)") (class "Default")
      (node (ref "C120") (pin "1") (pinfunction "1_1") (pintype "passive"))
      (node (ref "C170") (pin "1") (pinfunction "1_1") (pintype "passive"))
      (node (ref "R120") (pin "1") (pinfunction "1_1") (pintype "passive"))
      (node (ref "R70") (pin "2") (pinfunction "2_2") (pintype "passive"))
    )
    (net (code "72") (name "Net-(C121-Pad1)") (class "Default")
      (node (ref "C121") (pin "1") (pinfunction "1_1") (pintype "passive"))
      (node (ref "C171") (pin "1") (pinfunction "1_1") (pintype "passive"))
      (node (ref "R121") (pin "1") (pinfunction "1_1") (pintype "passive"))
      (node (ref "R71") (pin "2") (pinfunction "2_2") (pintype "passive"))
    )
    (net (code "73") (name "Net-(C122-Pad1)") (class "Default")
      (node (ref "C122") (pin "1") (pinfunction "1_1") (pintype "passive"))
      (node (ref "C172") (pin "1") (pinfunction "1_1") (pintype "passive"))
      (node (ref "R122") (pin "1") (pinfunction "1_1") (pintype "passive"))
      (node (ref "R72") (pin "2") (pinfunction "2_2") (pintype "passive"))
    )
    (net (code "74") (name "Net-(C123-Pad1)") (class "Default")
      (node (ref "C123") (pin "1") (pinfunction "1_1") (pintype "passive"))
      (node (ref "C173") (pin "1") (pinfunction "1_1") (pintype "passive"))
      (node (ref "R123") (pin "1") (pinfunction "1_1") (pintype "passive"))
      (node (ref "R73") (pin "2") (pinfunction "2_2") (pintype "passive"))
    )
    (net (code "75") (name "Net-(C124-Pad1)") (class "Default")
      (node (ref "C124") (pin "1") (pinfunction "1_1") (pintype "passive"))
      (node (ref "C174") (pin "1") (pinfunction "1_1") (pintype "passive"))
      (node (ref "R124") (pin "1") (pinfunction "1_1") (pintype "passive"))
      (node (ref "R74") (pin "2") (pinfunction "2_2") (pintype "passive"))
    )
    (net (code "76") (name "Net-(C125-Pad1)") (class "Default")
      (node (ref "C125") (pin "1") (pinfunction "1_1") (pintype "passive"))
      (node (ref "C175") (pin "1") (pinfunction "1_1") (pintype "passive"))
      (node (ref "R125") (pin "1") (pinfunction "1_1") (pintype "passive"))
      (node (ref "R75") (pin "2") (pinfunction "2_2") (pintype "passive"))
    )
    (net (code "77") (name "Net-(C126-Pad1)") (class "Default")
      (node (ref "C126") (pin "1") (pinfunction "1_1") (pintype "passive"))
      (node (ref "C176") (pin "1") (pinfunction "1_1") (pintype "passive"))
      (node (ref "R126") (pin "1") (pinfunction "1_1") (pintype "passive"))
      (node (ref "R76") (pin "2") (pinfunction "2_2") (pintype "passive"))
    )
    (net (code "78") (name "Net-(C127-Pad1)") (class "Default")
      (node (ref "C127") (pin "1") (pinfunction "1_1") (pintype "passive"))
      (node (ref "C177") (pin "1") (pinfunction "1_1") (pintype "passive"))
      (node (ref "R127") (pin "1") (pinfunction "1_1") (pintype "passive"))
      (node (ref "R77") (pin "2") (pinfunction "2_2") (pintype "passive"))
    )
    (net (code "79") (name "Net-(C128-Pad1)") (class "Default")
      (node (ref "C128") (pin "1") (pinfunction "1_1") (pintype "passive"))
      (node (ref "C178") (pin "1") (pinfunction "1_1") (pintype "passive"))
      (node (ref "R128") (pin "1") (pinfunction "1_1") (pintype "passive"))
      (node (ref "R78") (pin "2") (pinfunction "2_2") (pintype "passive"))
    )
    (net (code "80") (name "Net-(C129-Pad1)") (class "Default")
      (node (ref "C129") (pin "1") (pinfunction "1_1") (pintype "passive"))
      (node (ref "C179") (pin "1") (pinfunction "1_1") (pintype "passive"))
      (node (ref "R129") (pin "1") (pinfunction "1_1") (pintype "passive"))
      (node (ref "R79") (pin "2") (pinfunction "2_2") (pintype "passive"))
    )
    (net (code "81") (name "Net-(C130-Pad1)") (class "Default")
      (node (ref "C130") (pin "1") (pinfunction "1_1") (pintype "passive"))
      (node (ref "C180") (pin "1") (pinfunction "1_1") (pintype "passive"))
      (node (ref "R130") (pin "1") (pinfunction "1_1") (pintype "passive"))
      (node (ref "R80") (pin "2") (pinfunction "2_2") (pintype "passive"))
    )
    (net (code "82") (name "Net-(C131-Pad1)") (class "Default")
      (node (ref "C131") (pin "1") (pinfunction "1_1") (pintype "passive"))
      (node (ref "C181") (pin "1") (pinfunction "1_1") (pintype "passive"))
      (node (ref "R131") (pin "1") (pinfunction "1_1") (pintype "passive"))
      (node (ref "R81") (pin "2") (pinfunction "2_2") (pintype "passive"))
    )
    (net (code "83") (name "Net-(C132-Pad1)") (class "Default")
      (node (ref "C132") (pin "1") (pinfunction "1_1") (pintype "passive"))
      (node (ref "C182") (pin "1") (pinfunction "1_1") (pintype "passive"))
      (node (ref "R132") (pin "1") (pinfunction "1_1") (pintype "passive"))
      (node (ref "R82") (pin "2") (pinfunction "2_2") (pintype "passive"))
    )
    (net (code "84") (name "Net-(C133-Pad1)") (class "Default")
      (node (ref "C133") (pin "1") (pinfunction "1_1") (pintype "passive"))
      (node (ref "C183") (pin "1") (pinfunction "1_1") (pintype "passive"))
      (node (ref "R133") (pin "1") (pinfunction "1_1") (pintype "passive"))
      (node (ref "R83") (pin "2") (pinfunction "2_2") (pintype "passive"))
    )
    (net (code "85") (name "Net-(C134-Pad1)") (class "Default")
      (node (ref "C134") (pin "1") (pinfunction "1_1") (pintype "passive"))
      (node (ref "C184") (pin "1") (pinfunction "1_1") (pintype "passive"))
      (node (ref "R134") (pin "1") (pinfunction "1_1") (pintype "passive"))
      (node (ref "R84") (pin "2") (pinfunction "2_2") (pintype "passive"))
    )
    (net (code "86") (name "Net-(C135-Pad1)") (class "Default")
      (node (ref "C135") (pin "1") (pinfunction "1_1") (pintype "passive"))
      (node (ref "C185") (pin "1") (pinfunction "1_1") (pintype "passive"))
      (node (ref "R135") (pin "1") (pinfunction "1_1") (pintype "passive"))
      (node (ref "R85") (pin "2") (pinfunction "2_2") (pintype "passive"))
    )
    (net (code "87") (name "Net-(C136-Pad1)") (class "Default")
      (node (ref "C136") (pin "1") (pinfunction "1_1") (pintype "passive"))
      (node (ref "C186") (pin "1") (pinfunction "1_1") (pintype "passive"))
      (node (ref "R136") (pin "1") (pinfunction "1_1") (pintype "passive"))
      (node (ref "R86") (pin "2") (pinfunction "2_2") (pintype "passive"))
    )
    (net (code "88") (name "Net-(C137-Pad1)") (class "Default")
      (node (ref "C137") (pin "1") (pinfunction "1_1") (pintype "passive"))
      (node (ref "C187") (pin "1") (pinfunction "1_1") (pintype "passive"))
      (node (ref "R137") (pin "1") (pinfunction "1_1") (pintype "passive"))
      (node (ref "R87") (pin "2") (pinfunction "2_2") (pintype "passive"))
    )
    (net (code "89") (name "Net-(C138-Pad1)") (class "Default")
      (node (ref "C138") (pin "1") (pinfunction "1_1") (pintype "passive"))
      (node (ref "C188") (pin "1") (pinfunction "1_1") (pintype "passive"))
      (node (ref "R138") (pin "1") (pinfunction "1_1") (pintype "passive"))
      (node (ref "R88") (pin "2") (pinfunction "2_2") (pintype "passive"))
    )
    (net (code "90") (name "Net-(C139-Pad1)") (class "Default")
      (node (ref "C139") (pin "1") (pinfunction "1_1") (pintype "passive"))
      (node (ref "C189") (pin "1") (pinfunction "1_1") (pintype "passive"))
      (node (ref "R139") (pin "1") (pinfunction "1_1") (pintype "passive"))
      (node (ref "R89") (pin "2") (pinfunction "2_2") (pintype "passive"))
    )
    (net (code "91") (name "Net-(C140-Pad1)") (class "Default")
      (node (ref "C140") (pin "1") (pinfunction "1_1") (pintype "passive"))
      (node (ref "C190") (pin "1") (pinfunction "1_1") (pintype "passive"))
      (node (ref "R140") (pin "1") (pinfunction "1_1") (pintype "passive"))
      (node (ref "R90") (pin "2") (pinfunction "2_2") (pintype "passive"))
    )
    (net (code "92") (name "Net-(C141-Pad1)") (class "Default")
      (node (ref "C141") (pin "1") (pinfunction "1_1") (pintype "passive"))
      (node (ref "C191") (pin "1") (pinfunction "1_1") (pintype "passive"))
      (node (ref "R141") (pin "1") (pinfunction "1_1") (pintype "passive"))
      (node (ref "R91") (pin "2") (pinfunction "2_2") (pintype "passive"))
    )
    (net (code "93") (name "Net-(C142-Pad1)") (class "Default")
      (node (ref "C142") (pin "1") (pinfunction "1_1") (pintype "passive"))
      (node (ref "C192") (pin "1") (pinfunction "1_1") (pintype "passive"))
      (node (ref "R142") (pin "1") (pinfunction "1_1") (pintype "passive"))
      (node (ref "R92") (pin "2") (pinfunction "2_2") (pintype "passive"))
    )
    (net (code "94") (name "Net-(C143-Pad1)") (class "Default")
      (node (ref "C143") (pin "1") (pinfunction "1_1") (pintype "passive"))
      (node (ref "C193") (pin "1") (pinfunction "1_1") (pintype "passive"))
      (node (ref "R143") (pin "1") (pinfunction "1_1") (pintype "passive"))
      (node (ref "R93") (pin "2") (pinfunction "2_2") (pintype "passive"))
    )
    (net (code "95") (name "Net-(C144-Pad1)") (class "Default")
      (node (ref "C144") (pin "1") (pinfunction "1_1") (pintype "passive"))
      (node (ref "C194") (pin "1") (pinfunction "1_1") (pintype "passive"))
      (node (ref "R144") (pin "1") (pinfunction "1_1") (pintype "passive"))
      (node (ref "R94") (pin "2") (pinfunction "2_2") (pintype "passive"))
    )
    (net (code "96") (name "Net-(C145-Pad1)") (class "Default")
      (node (ref "C145") (pin "1") (pinfunction "1_1") (pintype "passive"))
      (node (ref "C195") (pin "1") (pinfunction "1_1") (pintype "passive"))
      (node (ref "R145") (pin "1") (pinfunction "1_1") (pintype "passive"))
      (node (ref "R95") (pin "2") (pinfunction "2_2") (pintype "passive"))
    )
    (net (code "97") (name "Net-(C146-Pad1)") (class "Default")
      (node (ref "C146") (pin "1") (pinfunction "1_1") (pintype "passive"))
      (node (ref "C196") (pin "1") (pinfunction "1_1") (pintype "passive"))
      (node (ref "R146") (pin "1") (pinfunction "1_1") (pintype "passive"))
      (node (ref "R96") (pin "2") (pinfunction "2_2") (pintype "passive"))
    )
    (net (code "98") (name "Net-(C147-Pad1)") (class "Default")
      (node (ref "C147") (pin "1") (pinfunction "1_1") (pintype "passive"))
      (node (ref "C197") (pin "1") (pinfunction "1_1") (pintype "passive"))
      (node (ref "R147") (pin "1") (pinfunction "1_1") (pintype "passive"))
      (node (ref "R97") (pin "2") (pinfunction "2_2") (pintype "passive"))
    )
    (net (code "99") (name "Net-(C148-Pad1)") (class "Default")
      (node (ref "C148") (pin "1") (pinfunction "1_1") (pintype "passive"))
      (node (ref "C198") (pin "1") (pinfunction "1_1") (pintype "passive"))
      (node (ref "R148") (pin "1") (pinfunction "1_1") (pintype "passive"))
      (node (ref "R98") (pin "2") (pinfunction "2_2") (pintype "passive"))
    )
    (net (code "100") (name "Net-(C149-Pad1)") (class "Default")
      (node (ref "C149") (pin "1") (pinfunction "1_1") (pintype "passive"))
      (node (ref "C199") (pin "1") (pinfunction "1_1") (pintype "passive"))
      (node (ref "R149") (pin "1") (pinfunction "1_1") (pintype "passive"))
      (node (ref "R99") (pin "2") (pinfunction "2_2") (pintype "passive"))
    )
    (net (code "101") (name "Net-(C150-Pad1)") (class "Default")
      (node (ref "C150") (pin "1") (pinfunction "1_1") (pintype "passive"))
      (node (ref "C200") (pin "1") (pinfunction "1_1") (pintype "passive"))
      (node (ref "R100") (pin "2") (pinfunction "2_2") (pintype "passive"))
      (node (ref "R150") (pin "1") (pinfunction "1_1") (pintype "passive"))
    )
    (net (code "102") (name "Net-(C201-Pad1)") (class "Default")
      (node (ref "C201") (pin "1") (pinfunction "1_1") (pintype "passive"))
      (node (ref "C251") (pin "1") (pinfunction "1_1") (pintype "passive"))
      (node (ref "J2") (pin "51") (pinfunction "51_51") (pintype "passive"))
      (node (ref "R101") (pin "2") (pinfunction "2_2") (pintype "passive"))
    )
    (net (code "103") (name "Net-(C202-Pad1)") (class "Default")
      (node (ref "C202") (pin "1") (pinfunction "1_1") (pintype "passive"))
      (node (ref "C252") (pin "1") (pinfunction "1_1") (pintype "passive"))
      (node (ref "J2") (pin "50") (pinfunction "50_50") (pintype "passive"))
      (node (ref "R102") (pin "2") (pinfunction "2_2") (pintype "passive"))
    )
    (net (code "104") (name "Net-(C203-Pad1)") (class "Default")
      (node (ref "C203") (pin "1") (pinfunction "1_1") (pintype "passive"))
      (node (ref "C253") (pin "1") (pinfunction "1_1") (pintype "passive"))
      (node (ref "J2") (pin "49") (pinfunction "49_49") (pintype "passive"))
      (node (ref "R103") (pin "2") (pinfunction "2_2") (pintype "passive"))
    )
    (net (code "105") (name "Net-(C204-Pad1)") (class "Default")
      (node (ref "C204") (pin "1") (pinfunction "1_1") (pintype "passive"))
      (node (ref "C254") (pin "1") (pinfunction "1_1") (pintype "passive"))
      (node (ref "J2") (pin "48") (pinfunction "48_48") (pintype "passive"))
      (node (ref "R104") (pin "2") (pinfunction "2_2") (pintype "passive"))
    )
    (net (code "106") (name "Net-(C205-Pad1)") (class "Default")
      (node (ref "C205") (pin "1") (pinfunction "1_1") (pintype "passive"))
      (node (ref "C255") (pin "1") (pinfunction "1_1") (pintype "passive"))
      (node (ref "J2") (pin "47") (pinfunction "47_47") (pintype "passive"))
      (node (ref "R105") (pin "2") (pinfunction "2_2") (pintype "passive"))
    )
    (net (code "107") (name "Net-(C206-Pad1)") (class "Default")
      (node (ref "C206") (pin "1") (pinfunction "1_1") (pintype "passive"))
      (node (ref "C256") (pin "1") (pinfunction "1_1") (pintype "passive"))
      (node (ref "J2") (pin "46") (pinfunction "46_46") (pintype "passive"))
      (node (ref "R106") (pin "2") (pinfunction "2_2") (pintype "passive"))
    )
    (net (code "108") (name "Net-(C207-Pad1)") (class "Default")
      (node (ref "C207") (pin "1") (pinfunction "1_1") (pintype "passive"))
      (node (ref "C257") (pin "1") (pinfunction "1_1") (pintype "passive"))
      (node (ref "J2") (pin "45") (pinfunction "45_45") (pintype "passive"))
      (node (ref "R107") (pin "2") (pinfunction "2_2") (pintype "passive"))
    )
    (net (code "109") (name "Net-(C208-Pad1)") (class "Default")
      (node (ref "C208") (pin "1") (pinfunction "1_1") (pintype "passive"))
      (node (ref "C258") (pin "1") (pinfunction "1_1") (pintype "passive"))
      (node (ref "J2") (pin "44") (pinfunction "44_44") (pintype "passive"))
      (node (ref "R108") (pin "2") (pinfunction "2_2") (pintype "passive"))
    )
    (net (code "110") (name "Net-(C209-Pad1)") (class "Default")
      (node (ref "C209") (pin "1") (pinfunction "1_1") (pintype "passive"))
      (node (ref "C259") (pin "1") (pinfunction "1_1") (pintype "passive"))
      (node (ref "J2") (pin "43") (pinfunction "43_43") (pintype "passive"))
      (node (ref "R109") (pin "2") (pinfunction "2_2") (pintype "passive"))
    )
    (net (code "111") (name "Net-(C210-Pad1)") (class "Default")
      (node (ref "C210") (pin "1") (pinfunction "1_1") (pintype "passive"))
      (node (ref "C260") (pin "1") (pinfunction "1_1") (pintype "passive"))
      (node (ref "J2") (pin "42") (pinfunction "42_42") (pintype "passive"))
      (node (ref "R110") (pin "2") (pinfunction "2_2") (pintype "passive"))
    )
    (net (code "112") (name "Net-(C211-Pad1)") (class "Default")
      (node (ref "C211") (pin "1") (pinfunction "1_1") (pintype "passive"))
      (node (ref "C261") (pin "1") (pinfunction "1_1") (pintype "passive"))
      (node (ref "J2") (pin "41") (pinfunction "41_41") (pintype "passive"))
      (node (ref "R111") (pin "2") (pinfunction "2_2") (pintype "passive"))
    )
    (net (code "113") (name "Net-(C212-Pad1)") (class "Default")
      (node (ref "C212") (pin "1") (pinfunction "1_1") (pintype "passive"))
      (node (ref "C262") (pin "1") (pinfunction "1_1") (pintype "passive"))
      (node (ref "J2") (pin "40") (pinfunction "40_40") (pintype "passive"))
      (node (ref "R112") (pin "2") (pinfunction "2_2") (pintype "passive"))
    )
    (net (code "114") (name "Net-(C213-Pad1)") (class "Default")
      (node (ref "C213") (pin "1") (pinfunction "1_1") (pintype "passive"))
      (node (ref "C263") (pin "1") (pinfunction "1_1") (pintype "passive"))
      (node (ref "J2") (pin "39") (pinfunction "39_39") (pintype "passive"))
      (node (ref "R113") (pin "2") (pinfunction "2_2") (pintype "passive"))
    )
    (net (code "115") (name "Net-(C214-Pad1)") (class "Default")
      (node (ref "C214") (pin "1") (pinfunction "1_1") (pintype "passive"))
      (node (ref "C264") (pin "1") (pinfunction "1_1") (pintype "passive"))
      (node (ref "J2") (pin "38") (pinfunction "38_38") (pintype "passive"))
      (node (ref "R114") (pin "2") (pinfunction "2_2") (pintype "passive"))
    )
    (net (code "116") (name "Net-(C215-Pad1)") (class "Default")
      (node (ref "C215") (pin "1") (pinfunction "1_1") (pintype "passive"))
      (node (ref "C265") (pin "1") (pinfunction "1_1") (pintype "passive"))
      (node (ref "J2") (pin "37") (pinfunction "37_37") (pintype "passive"))
      (node (ref "R115") (pin "2") (pinfunction "2_2") (pintype "passive"))
    )
    (net (code "117") (name "Net-(C216-Pad1)") (class "Default")
      (node (ref "C216") (pin "1") (pinfunction "1_1") (pintype "passive"))
      (node (ref "C266") (pin "1") (pinfunction "1_1") (pintype "passive"))
      (node (ref "J2") (pin "36") (pinfunction "36_36") (pintype "passive"))
      (node (ref "R116") (pin "2") (pinfunction "2_2") (pintype "passive"))
    )
    (net (code "118") (name "Net-(C217-Pad1)") (class "Default")
      (node (ref "C217") (pin "1") (pinfunction "1_1") (pintype "passive"))
      (node (ref "C267") (pin "1") (pinfunction "1_1") (pintype "passive"))
      (node (ref "J2") (pin "35") (pinfunction "35_35") (pintype "passive"))
      (node (ref "R117") (pin "2") (pinfunction "2_2") (pintype "passive"))
    )
    (net (code "119") (name "Net-(C218-Pad1)") (class "Default")
      (node (ref "C218") (pin "1") (pinfunction "1_1") (pintype "passive"))
      (node (ref "C268") (pin "1") (pinfunction "1_1") (pintype "passive"))
      (node (ref "J2") (pin "34") (pinfunction "34_34") (pintype "passive"))
      (node (ref "R118") (pin "2") (pinfunction "2_2") (pintype "passive"))
    )
    (net (code "120") (name "Net-(C219-Pad1)") (class "Default")
      (node (ref "C219") (pin "1") (pinfunction "1_1") (pintype "passive"))
      (node (ref "C269") (pin "1") (pinfunction "1_1") (pintype "passive"))
      (node (ref "J2") (pin "33") (pinfunction "33_33") (pintype "passive"))
      (node (ref "R119") (pin "2") (pinfunction "2_2") (pintype "passive"))
    )
    (net (code "121") (name "Net-(C220-Pad1)") (class "Default")
      (node (ref "C220") (pin "1") (pinfunction "1_1") (pintype "passive"))
      (node (ref "C270") (pin "1") (pinfunction "1_1") (pintype "passive"))
      (node (ref "J2") (pin "32") (pinfunction "32_32") (pintype "passive"))
      (node (ref "R120") (pin "2") (pinfunction "2_2") (pintype "passive"))
    )
    (net (code "122") (name "Net-(C221-Pad1)") (class "Default")
      (node (ref "C221") (pin "1") (pinfunction "1_1") (pintype "passive"))
      (node (ref "C271") (pin "1") (pinfunction "1_1") (pintype "passive"))
      (node (ref "J2") (pin "31") (pinfunction "31_31") (pintype "passive"))
      (node (ref "R121") (pin "2") (pinfunction "2_2") (pintype "passive"))
    )
    (net (code "123") (name "Net-(C222-Pad1)") (class "Default")
      (node (ref "C222") (pin "1") (pinfunction "1_1") (pintype "passive"))
      (node (ref "C272") (pin "1") (pinfunction "1_1") (pintype "passive"))
      (node (ref "J2") (pin "30") (pinfunction "30_30") (pintype "passive"))
      (node (ref "R122") (pin "2") (pinfunction "2_2") (pintype "passive"))
    )
    (net (code "124") (name "Net-(C223-Pad1)") (class "Default")
      (node (ref "C223") (pin "1") (pinfunction "1_1") (pintype "passive"))
      (node (ref "C273") (pin "1") (pinfunction "1_1") (pintype "passive"))
      (node (ref "J2") (pin "29") (pinfunction "29_29") (pintype "passive"))
      (node (ref "R123") (pin "2") (pinfunction "2_2") (pintype "passive"))
    )
    (net (code "125") (name "Net-(C224-Pad1)") (class "Default")
      (node (ref "C224") (pin "1") (pinfunction "1_1") (pintype "passive"))
      (node (ref "C274") (pin "1") (pinfunction "1_1") (pintype "passive"))
      (node (ref "J2") (pin "28") (pinfunction "28_28") (pintype "passive"))
      (node (ref "R124") (pin "2") (pinfunction "2_2") (pintype "passive"))
    )
    (net (code "126") (name "Net-(C225-Pad1)") (class "Default")
      (node (ref "C225") (pin "1") (pinfunction "1_1") (pintype "passive"))
      (node (ref "C275") (pin "1") (pinfunction "1_1") (pintype "passive"))
      (node (ref "J2") (pin "27") (pinfunction "27_27") (pintype "passive"))
      (node (ref "R125") (pin "2") (pinfunction "2_2") (pintype "passive"))
    )
    (net (code "127") (name "Net-(C226-Pad1)") (class "Default")
      (node (ref "C226") (pin "1") (pinfunction "1_1") (pintype "passive"))
      (node (ref "C276") (pin "1") (pinfunction "1_1") (pintype "passive"))
      (node (ref "J2") (pin "26") (pinfunction "26_26") (pintype "passive"))
      (node (ref "R126") (pin "2") (pinfunction "2_2") (pintype "passive"))
    )
    (net (code "128") (name "Net-(C227-Pad1)") (class "Default")
      (node (ref "C227") (pin "1") (pinfunction "1_1") (pintype "passive"))
      (node (ref "C277") (pin "1") (pinfunction "1_1") (pintype "passive"))
      (node (ref "J2") (pin "25") (pinfunction "25_25") (pintype "passive"))
      (node (ref "R127") (pin "2") (pinfunction "2_2") (pintype "passive"))
    )
    (net (code "129") (name "Net-(C228-Pad1)") (class "Default")
      (node (ref "C228") (pin "1") (pinfunction "1_1") (pintype "passive"))
      (node (ref "C278") (pin "1") (pinfunction "1_1") (pintype "passive"))
      (node (ref "J2") (pin "24") (pinfunction "24_24") (pintype "passive"))
      (node (ref "R128") (pin "2") (pinfunction "2_2") (pintype "passive"))
    )
    (net (code "130") (name "Net-(C229-Pad1)") (class "Default")
      (node (ref "C229") (pin "1") (pinfunction "1_1") (pintype "passive"))
      (node (ref "C279") (pin "1") (pinfunction "1_1") (pintype "passive"))
      (node (ref "J2") (pin "23") (pinfunction "23_23") (pintype "passive"))
      (node (ref "R129") (pin "2") (pinfunction "2_2") (pintype "passive"))
    )
    (net (code "131") (name "Net-(C230-Pad1)") (class "Default")
      (node (ref "C230") (pin "1") (pinfunction "1_1") (pintype "passive"))
      (node (ref "C280") (pin "1") (pinfunction "1_1") (pintype "passive"))
      (node (ref "J2") (pin "22") (pinfunction "22_22") (pintype "passive"))
      (node (ref "R130") (pin "2") (pinfunction "2_2") (pintype "passive"))
    )
    (net (code "132") (name "Net-(C231-Pad1)") (class "Default")
      (node (ref "C231") (pin "1") (pinfunction "1_1") (pintype "passive"))
      (node (ref "C281") (pin "1") (pinfunction "1_1") (pintype "passive"))
      (node (ref "J2") (pin "21") (pinfunction "21_21") (pintype "passive"))
      (node (ref "R131") (pin "2") (pinfunction "2_2") (pintype "passive"))
    )
    (net (code "133") (name "Net-(C232-Pad1)") (class "Default")
      (node (ref "C232") (pin "1") (pinfunction "1_1") (pintype "passive"))
      (node (ref "C282") (pin "1") (pinfunction "1_1") (pintype "passive"))
      (node (ref "J2") (pin "20") (pinfunction "20_20") (pintype "passive"))
      (node (ref "R132") (pin "2") (pinfunction "2_2") (pintype "passive"))
    )
    (net (code "134") (name "Net-(C233-Pad1)") (class "Default")
      (node (ref "C233") (pin "1") (pinfunction "1_1") (pintype "passive"))
      (node (ref "C283") (pin "1") (pinfunction "1_1") (pintype "passive"))
      (node (ref "J2") (pin "19") (pinfunction "19_19") (pintype "passive"))
      (node (ref "R133") (pin "2") (pinfunction "2_2") (pintype "passive"))
    )
    (net (code "135") (name "Net-(C234-Pad1)") (class "Default")
      (node (ref "C234") (pin "1") (pinfunction "1_1") (pintype "passive"))
      (node (ref "C284") (pin "1") (pinfunction "1_1") (pintype "passive"))
      (node (ref "J2") (pin "18") (pinfunction "18_18") (pintype "passive"))
      (node (ref "R134") (pin "2") (pinfunction "2_2") (pintype "passive"))
    )
    (net (code "136") (name "Net-(C235-Pad1)") (class "Default")
      (node (ref "C235") (pin "1") (pinfunction "1_1") (pintype "passive"))
      (node (ref "C285") (pin "1") (pinfunction "1_1") (pintype "passive"))
      (node (ref "J2") (pin "17") (pinfunction "17_17") (pintype "passive"))
      (node (ref "R135") (pin "2") (pinfunction "2_2") (pintype "passive"))
    )
    (net (code "137") (name "Net-(C236-Pad1)") (class "Default")
      (node (ref "C236") (pin "1") (pinfunction "1_1") (pintype "passive"))
      (node (ref "C286") (pin "1") (pinfunction "1_1") (pintype "passive"))
      (node (ref "J2") (pin "16") (pinfunction "16_16") (pintype "passive"))
      (node (ref "R136") (pin "2") (pinfunction "2_2") (pintype "passive"))
    )
    (net (code "138") (name "Net-(C237-Pad1)") (class "Default")
      (node (ref "C237") (pin "1") (pinfunction "1_1") (pintype "passive"))
      (node (ref "C287") (pin "1") (pinfunction "1_1") (pintype "passive"))
      (node (ref "J2") (pin "15") (pinfunction "15_15") (pintype "passive"))
      (node (ref "R137") (pin "2") (pinfunction "2_2") (pintype "passive"))
    )
    (net (code "139") (name "Net-(C238-Pad1)") (class "Default")
      (node (ref "C238") (pin "1") (pinfunction "1_1") (pintype "passive"))
      (node (ref "C288") (pin "1") (pinfunction "1_1") (pintype "passive"))
      (node (ref "J2") (pin "14") (pinfunction "14_14") (pintype "passive"))
      (node (ref "R138") (pin "2") (pinfunction "2_2") (pintype "passive"))
    )
    (net (code "140") (name "Net-(C239-Pad1)") (class "Default")
      (node (ref "C239") (pin "1") (pinfunction "1_1") (pintype "passive"))
      (node (ref "C289") (pin "1") (pinfunction "1_1") (pintype "passive"))
      (node (ref "J2") (pin "13") (pinfunction "13_13") (pintype "passive"))
      (node (ref "R139") (pin "2") (pinfunction "2_2") (pintype "passive"))
    )
    (net (code "141") (name "Net-(C240-Pad1)") (class "Default")
      (node (ref "C240") (pin "1") (pinfunction "1_1") (pintype "passive"))
      (node (ref "C290") (pin "1") (pinfunction "1_1") (pintype "passive"))
      (node (ref "J2") (pin "12") (pinfunction "12_12") (pintype "passive"))
      (node (ref "R140") (pin "2") (pinfunction "2_2") (pintype "passive"))
    )
    (net (code "142") (name "Net-(C241-Pad1)") (class "Default")
      (node (ref "C241") (pin "1") (pinfunction "1_1") (pintype "passive"))
      (node (ref "C291") (pin "1") (pinfunction "1_1") (pintype "passive"))
      (node (ref "J2") (pin "11") (pinfunction "11_11") (pintype "passive"))
      (node (ref "R141") (pin "2") (pinfunction "2_2") (pintype "passive"))
    )
    (net (code "143") (name "Net-(C242-Pad1)") (class "Default")
      (node (ref "C242") (pin "1") (pinfunction "1_1") (pintype "passive"))
      (node (ref "C292") (pin "1") (pinfunction "1_1") (pintype "passive"))
      (node (ref "J2") (pin "10") (pinfunction "10_10") (pintype "passive"))
      (node (ref "R142") (pin "2") (pinfunction "2_2") (pintype "passive"))
    )
    (net (code "144") (name "Net-(C243-Pad1)") (class "Default")
      (node (ref "C243") (pin "1") (pinfunction "1_1") (pintype "passive"))
      (node (ref "C293") (pin "1") (pinfunction "1_1") (pintype "passive"))
      (node (ref "J2") (pin "9") (pinfunction "9_9") (pintype "passive"))
      (node (ref "R143") (pin "2") (pinfunction "2_2") (pintype "passive"))
    )
    (net (code "145") (name "Net-(C244-Pad1)") (class "Default")
      (node (ref "C244") (pin "1") (pinfunction "1_1") (pintype "passive"))
      (node (ref "C294") (pin "1") (pinfunction "1_1") (pintype "passive"))
      (node (ref "J2") (pin "8") (pinfunction "8_8") (pintype "passive"))
      (node (ref "R144") (pin "2") (pinfunction "2_2") (pintype "passive"))
    )
    (net (code "146") (name "Net-(C245-Pad1)") (class "Default")
      (node (ref "C245") (pin "1") (pinfunction "1_1") (pintype "passive"))
      (node (ref "C295") (pin "1") (pinfunction "1_1") (pintype "passive"))
      (node (ref "J2") (pin "7") (pinfunction "7_7") (pintype "passive"))
      (node (ref "R145") (pin "2") (pinfunction "2_2") (pintype "passive"))
    )
    (net (code "147") (name "Net-(C246-Pad1)") (class "Default")
      (node (ref "C246") (pin "1") (pinfunction "1_1") (pintype "passive"))
      (node (ref "C296") (pin "1") (pinfunction "1_1") (pintype "passive"))
      (node (ref "J2") (pin "6") (pinfunction "6_6") (pintype "passive"))
      (node (ref "R146") (pin "2") (pinfunction "2_2") (pintype "passive"))
    )
    (net (code "148") (name "Net-(C247-Pad1)") (class "Default")
      (node (ref "C247") (pin "1") (pinfunction "1_1") (pintype "passive"))
      (node (ref "C297") (pin "1") (pinfunction "1_1") (pintype "passive"))
      (node (ref "J2") (pin "5") (pinfunction "5_5") (pintype "passive"))
      (node (ref "R147") (pin "2") (pinfunction "2_2") (pintype "passive"))
    )
    (net (code "149") (name "Net-(C248-Pad1)") (class "Default")
      (node (ref "C248") (pin "1") (pinfunction "1_1") (pintype "passive"))
      (node (ref "C298") (pin "1") (pinfunction "1_1") (pintype "passive"))
      (node (ref "J2") (pin "4") (pinfunction "4_4") (pintype "passive"))
      (node (ref "R148") (pin "2") (pinfunction "2_2") (pintype "passive"))
    )
    (net (code "150") (name "Net-(C249-Pad1)") (class "Default")
      (node (ref "C249") (pin "1") (pinfunction "1_1") (pintype "passive"))
      (node (ref "C299") (pin "1") (pinfunction "1_1") (pintype "passive"))
      (node (ref "J2") (pin "3") (pinfunction "3_3") (pintype "passive"))
      (node (ref "R149") (pin "2") (pinfunction "2_2") (pintype "passive"))
    )
    (net (code "151") (name "Net-(C250-Pad1)") (class "Default")
      (node (ref "C250") (pin "1") (pinfunction "1_1") (pintype "passive"))
      (node (ref "C300") (pin "1") (pinfunction "1_1") (pintype "passive"))
      (node (ref "J2") (pin "2") (pinfunction "2_2") (pintype "passive"))
      (node (ref "R150") (pin "2") (pinfunction "2_2") (pintype "passive"))
    )
    (net (code "152") (name "Net-(J1-Pad1)") (class "Default")
      (node (ref "J1") (pin "1") (pinfunction "1_1") (pintype "passive"))
      (node (ref "R1") (pin "1") (pinfunction "1_1") (pintype "passive"))
    )
    (net (code "153") (name "Net-(J1-Pad2)") (class "Default")
      (node (ref "J1") (pin "2") (pinfunction "2_2") (pintype "passive"))
      (node (ref "R2") (pin "1") (pinfunction "1_1") (pintype "passive"))
    )
    (net (code "154") (name "Net-(J1-Pad3)") (class "Default")
      (node (ref "J1") (pin "3") (pinfunction "3_3") (pintype "passive"))
      (node (ref "R3") (pin "1") (pinfunction "1_1") (pintype "passive"))
    )
    (net (code "155") (name "Net-(J1-Pad4)") (class "Default")
      (node (ref "J1") (pin "4") (pinfunction "4_4") (pintype "passive"))
      (node (ref "R4") (pin "1") (pinfunction "1_1") (pintype "passive"))
    )
    (net (code "156") (name "Net-(J1-Pad5)") (class "Default")
      (node (ref "J1") (pin "5") (pinfunction "5_5") (pintype "passive"))
      (node (ref "R5") (pin "1") (pinfunction "1_1") (pintype "passive"))
    )
    (net (code "157") (name "Net-(J1-Pad6)") (class "Default")
      (node (ref "J1") (pin "6") (pinfunction "6_6") (pintype "passive"))
      (node (ref "R6") (pin "1") (pinfunction "1_1") (pintype "passive"))
    )
    (net (code "158") (name "Net-(J1-Pad7)") (class "Default")
      (node (ref "J1") (pin "7") (pinfunction "7_7") (pintype "passive"))
      (node (ref "R7") (pin "1") (pinfunction "1_1") (pintype "passive"))
    )
    (net (code "159") (name "Net-(J1-Pad8)") (class "Default")
      (node (ref "J1") (pin "8") (pinfunction "8_8") (pintype "passive"))
      (node (ref "R8") (pin "1") (pinfunction "1_1") (pintype "passive"))
    )
    (net (code "160") (name "Net-(J1-Pad9)") (class "Default")
      (node (ref "J1") (pin "9") (pinfunction "9_9") (pintype "passive"))
      (node (ref "R9") (pin "1") (pinfunction "1_1") (pintype "passive"))
    )
    (net (code "161") (name "Net-(J1-Pad10)") (class "Default")
      (node (ref "J1") (pin "10") (pinfunction "10_10") (pintype "passive"))
      (node (ref "R10") (pin "1") (pinfunction "1_1") (pintype "passive"))
    )
    (net (code "162") (name "Net-(J1-Pad11)") (class "Default")
      (node (ref "J1") (pin "11") (pinfunction "11_11") (pintype "passive"))
      (node (ref "R11") (pin "1") (pinfunction "1_1") (pintype "passive"))
    )
    (net (code "163") (name "Net-(J1-Pad12)") (class "Default")
      (node (ref "J1") (pin "12") (pinfunction "12_12") (pintype "passive"))
      (node (ref "R12") (pin "1") (pinfunction "1_1") (pintype "passive"))
    )
    (net (code "164") (name "Net-(J1-Pad13)") (class "Default")
      (node (ref "J1") (pin "13") (pinfunction "13_13") (pintype "passive"))
      (node (ref "R13") (pin "1") (pinfunction "1_1") (pintype "passive"))
    )
    (net (code "165") (name "Net-(J1-Pad14)") (class "Default")
      (node (ref "J1") (pin "14") (pinfunction "14_14") (pintype "passive"))
      (node (ref "R14") (pin "1") (pinfunction "1_1") (pintype "passive"))
    )
    (net (code "166") (name "Net-(J1-Pad15)") (class "Default")
      (node (ref "J1") (pin "15") (pinfunction "15_15") (pintype "passive"))
      (node (ref "R15") (pin "1") (pinfunction "1_1") (pintype "passive"))
    )
    (net (code "167") (name "Net-(J1-Pad16)") (class "Default")
      (node (ref "J1") (pin "16") (pinfunction "16_16") (pintype "passive"))
      (node (ref "R16") (pin "1") (pinfunction "1_1") (pintype "passive"))
    )
    (net (code "168") (name "Net-(J1-Pad17)") (class "Default")
      (node (ref "J1") (pin "17") (pinfunction "17_17") (pintype "passive"))
      (node (ref "R17") (pin "1") (pinfunction "1_1") (pintype "passive"))
    )
    (net (code "169") (name "Net-(J1-Pad18)") (class "Default")
      (node (ref "J1") (pin "18") (pinfunction "18_18") (pintype "passive"))
      (node (ref "R18") (pin "1") (pinfunction "1_1") (pintype "passive"))
    )
    (net (code "170") (name "Net-(J1-Pad19)") (class "Default")
      (node (ref "J1") (pin "19") (pinfunction "19_19") (pintype "passive"))
      (node (ref "R19") (pin "1") (pinfunction "1_1") (pintype "passive"))
    )
    (net (code "171") (name "Net-(J1-Pad20)") (class "Default")
      (node (ref "J1") (pin "20") (pinfunction "20_20") (pintype "passive"))
      (node (ref "R20") (pin "1") (pinfunction "1_1") (pintype "passive"))
    )
    (net (code "172") (name "Net-(J1-Pad21)") (class "Default")
      (node (ref "J1") (pin "21") (pinfunction "21_21") (pintype "passive"))
      (node (ref "R21") (pin "1") (pinfunction "1_1") (pintype "passive"))
    )
    (net (code "173") (name "Net-(J1-Pad22)") (class "Default")
      (node (ref "J1") (pin "22") (pinfunction "22_22") (pintype "passive"))
      (node (ref "R22") (pin "1") (pinfunction "1_1") (pintype "passive"))
    )
    (net (code "174") (name "Net-(J1-Pad23)") (class "Default")
      (node (ref "J1") (pin "23") (pinfunction "23_23") (pintype "passive"))
      (node (ref "R23") (pin "1") (pinfunction "1_1") (pintype "passive"))
    )
    (net (code "175") (name "Net-(J1-Pad24)") (class "Default")
      (node (ref "J1") (pin "24") (pinfunction "24_24") (pintype "passive"))
      (node (ref "R24") (pin "1") (pinfunction "1_1") (pintype "passive"))
    )
    (net (code "176") (name "Net-(J1-Pad25)") (class "Default")
      (node (ref "J1") (pin "25") (pinfunction "25_25") (pintype "passive"))
      (node (ref "R25") (pin "1") (pinfunction "1_1") (pintype "passive"))
    )
    (net (code "177") (name "Net-(J1-Pad26)") (class "Default")
      (node (ref "J1") (pin "26") (pinfunction "26_26") (pintype "passive"))
      (node (ref "R26") (pin "1") (pinfunction "1_1") (pintype "passive"))
    )
    (net (code "178") (name "Net-(J1-Pad27)") (class "Default")
      (node (ref "J1") (pin "27") (pinfunction "27_27") (pintype "passive"))
      (node (ref "R27") (pin "1") (pinfunction "1_1") (pintype "passive"))
    )
    (net (code "179") (name "Net-(J1-Pad28)") (class "Default")
      (node (ref "J1") (pin "28") (pinfunction "28_28") (pintype "passive"))
      (node (ref "R28") (pin "1") (pinfunction "1_1") (pintype "passive"))
    )
    (net (code "180") (name "Net-(J1-Pad29)") (class "Default")
      (node (ref "J1") (pin "29") (pinfunction "29_29") (pintype "passive"))
      (node (ref "R29") (pin "1") (pinfunction "1_1") (pintype "passive"))
    )
    (net (code "181") (name "Net-(J1-Pad30)") (class "Default")
      (node (ref "J1") (pin "30") (pinfunction "30_30") (pintype "passive"))
      (node (ref "R30") (pin "1") (pinfunction "1_1") (pintype "passive"))
    )
    (net (code "182") (name "Net-(J1-Pad31)") (class "Default")
      (node (ref "J1") (pin "31") (pinfunction "31_31") (pintype "passive"))
      (node (ref "R31") (pin "1") (pinfunction "1_1") (pintype "passive"))
    )
    (net (code "183") (name "Net-(J1-Pad32)") (class "Default")
      (node (ref "J1") (pin "32") (pinfunction "32_32") (pintype "passive"))
      (node (ref "R32") (pin "1") (pinfunction "1_1") (pintype "passive"))
    )
    (net (code "184") (name "Net-(J1-Pad33)") (class "Default")
      (node (ref "J1") (pin "33") (pinfunction "33_33") (pintype "passive"))
      (node (ref "R33") (pin "1") (pinfunction "1_1") (pintype "passive"))
    )
    (net (code "185") (name "Net-(J1-Pad34)") (class "Default")
      (node (ref "J1") (pin "34") (pinfunction "34_34") (pintype "passive"))
      (node (ref "R34") (pin "1") (pinfunction "1_1") (pintype "passive"))
    )
    (net (code "186") (name "Net-(J1-Pad35)") (class "Default")
      (node (ref "J1") (pin "35") (pinfunction "35_35") (pintype "passive"))
      (node (ref "R35") (pin "1") (pinfunction "1_1") (pintype "passive"))
    )
    (net (code "187") (name "Net-(J1-Pad36)") (class "Default")
      (node (ref "J1") (pin "36") (pinfunction "36_36") (pintype "passive"))
      (node (ref "R36") (pin "1") (pinfunction "1_1") (pintype "passive"))
    )
    (net (code "188") (name "Net-(J1-Pad37)") (class "Default")
      (node (ref "J1") (pin "37") (pinfunction "37_37") (pintype "passive"))
      (node (ref "R37") (pin "1") (pinfunction "1_1") (pintype "passive"))
    )
    (net (code "189") (name "Net-(J1-Pad38)") (class "Default")
      (node (ref "J1") (pin "38") (pinfunction "38_38") (pintype "passive"))
      (node (ref "R38") (pin "1") (pinfunction "1_1") (pintype "passive"))
    )
    (net (code "190") (name "Net-(J1-Pad39)") (class "Default")
      (node (ref "J1") (pin "39") (pinfunction "39_39") (pintype "passive"))
      (node (ref "R39") (pin "1") (pinfunction "1_1") (pintype "passive"))
    )
    (net (code "191") (name "Net-(J1-Pad40)") (class "Default")
      (node (ref "J1") (pin "40") (pinfunction "40_40") (pintype "passive"))
      (node (ref "R40") (pin "1") (pinfunction "1_1") (pintype "passive"))
    )
    (net (code "192") (name "Net-(J1-Pad41)") (class "Default")
      (node (ref "J1") (pin "41") (pinfunction "41_41") (pintype "passive"))
      (node (ref "R41") (pin "1") (pinfunction "1_1") (pintype "passive"))
    )
    (net (code "193") (name "Net-(J1-Pad42)") (class "Default")
      (node (ref "J1") (pin "42") (pinfunction "42_42") (pintype "passive"))
      (node (ref "R42") (pin "1") (pinfunction "1_1") (pintype "passive"))
    )
    (net (code "194") (name "Net-(J1-Pad43)") (class "Default")
      (node (ref "J1") (pin "43") (pinfunction "43_43") (pintype "passive"))
      (node (ref "R43") (pin "1") (pinfunction "1_1") (pintype "passive"))
    )
    (net (code "195") (name "Net-(J1-Pad44)") (class "Default")
      (node (ref "J1") (pin "44") (pinfunction "44_44") (pintype "passive"))
      (node (ref "R44") (pin "1") (pinfunction "1_1") (pintype "passive"))
    )
    (net (code "196") (name "Net-(J1-Pad45)") (class "Default")
      (node (ref "J1") (pin "45") (pinfunction "45_45") (pintype "passive"))
      (node (ref "R45") (pin "1") (pinfunction "1_1") (pintype "passive"))
    )
    (net (code "197") (name "Net-(J1-Pad46)") (class "Default")
      (node (ref "J1") (pin "46") (pinfunction "46_46") (pintype "passive"))
      (node (ref "R46") (pin "1") (pinfunction "1_1") (pintype "passive"))
    )
    (net (code "198") (name "Net-(J1-Pad47)") (class "Default")
      (node (ref "J1") (pin "47") (pinfunction "47_47") (pintype "passive"))
      (node (ref "R47") (pin "1") (pinfunction "1_1") (pintype "passive"))
    )
    (net (code "199") (name "Net-(J1-Pad48)") (class "Default")
      (node (ref "J1") (pin "48") (pinfunction "48_48") (pintype "passive"))
      (node (ref "R48") (pin "1") (pinfunction "1_1") (pintype "passive"))
    )
    (net (code "200") (name "Net-(J1-Pad49)") (class "Default")
      (node (ref "J1") (pin "49") (pinfunction "49_49") (pintype "passive"))
      (node (ref "R49") (pin "1") (pinfunction "1_1") (pintype "passive"))
    )
    (net (code "201") (name "Net-(J1-Pad50)") (class "Default")
      (node (ref "J1") (pin "50") (pinfunction "50_50") (pintype "passive"))
      (node (ref "R50") (pin "1") (pinfunction "1_1") (pintype "passive"))
    )
    (net (code "202") (name "unconnected-(J1-Pad51)") (class "Default")
      (node (ref "J1") (pin "51") (pinfunction "51_51") (pintype "passive"))
    )
    (net (code "203") (name "unconnected-(J2-Pad1)") (class "Default")
      (node (ref "J2") (pin "1") (pinfunction "1_1") (pintype "passive"))
    )
  )
)
